# range_cape.net
KiCad netlist of a schematic drawn in EAGLE
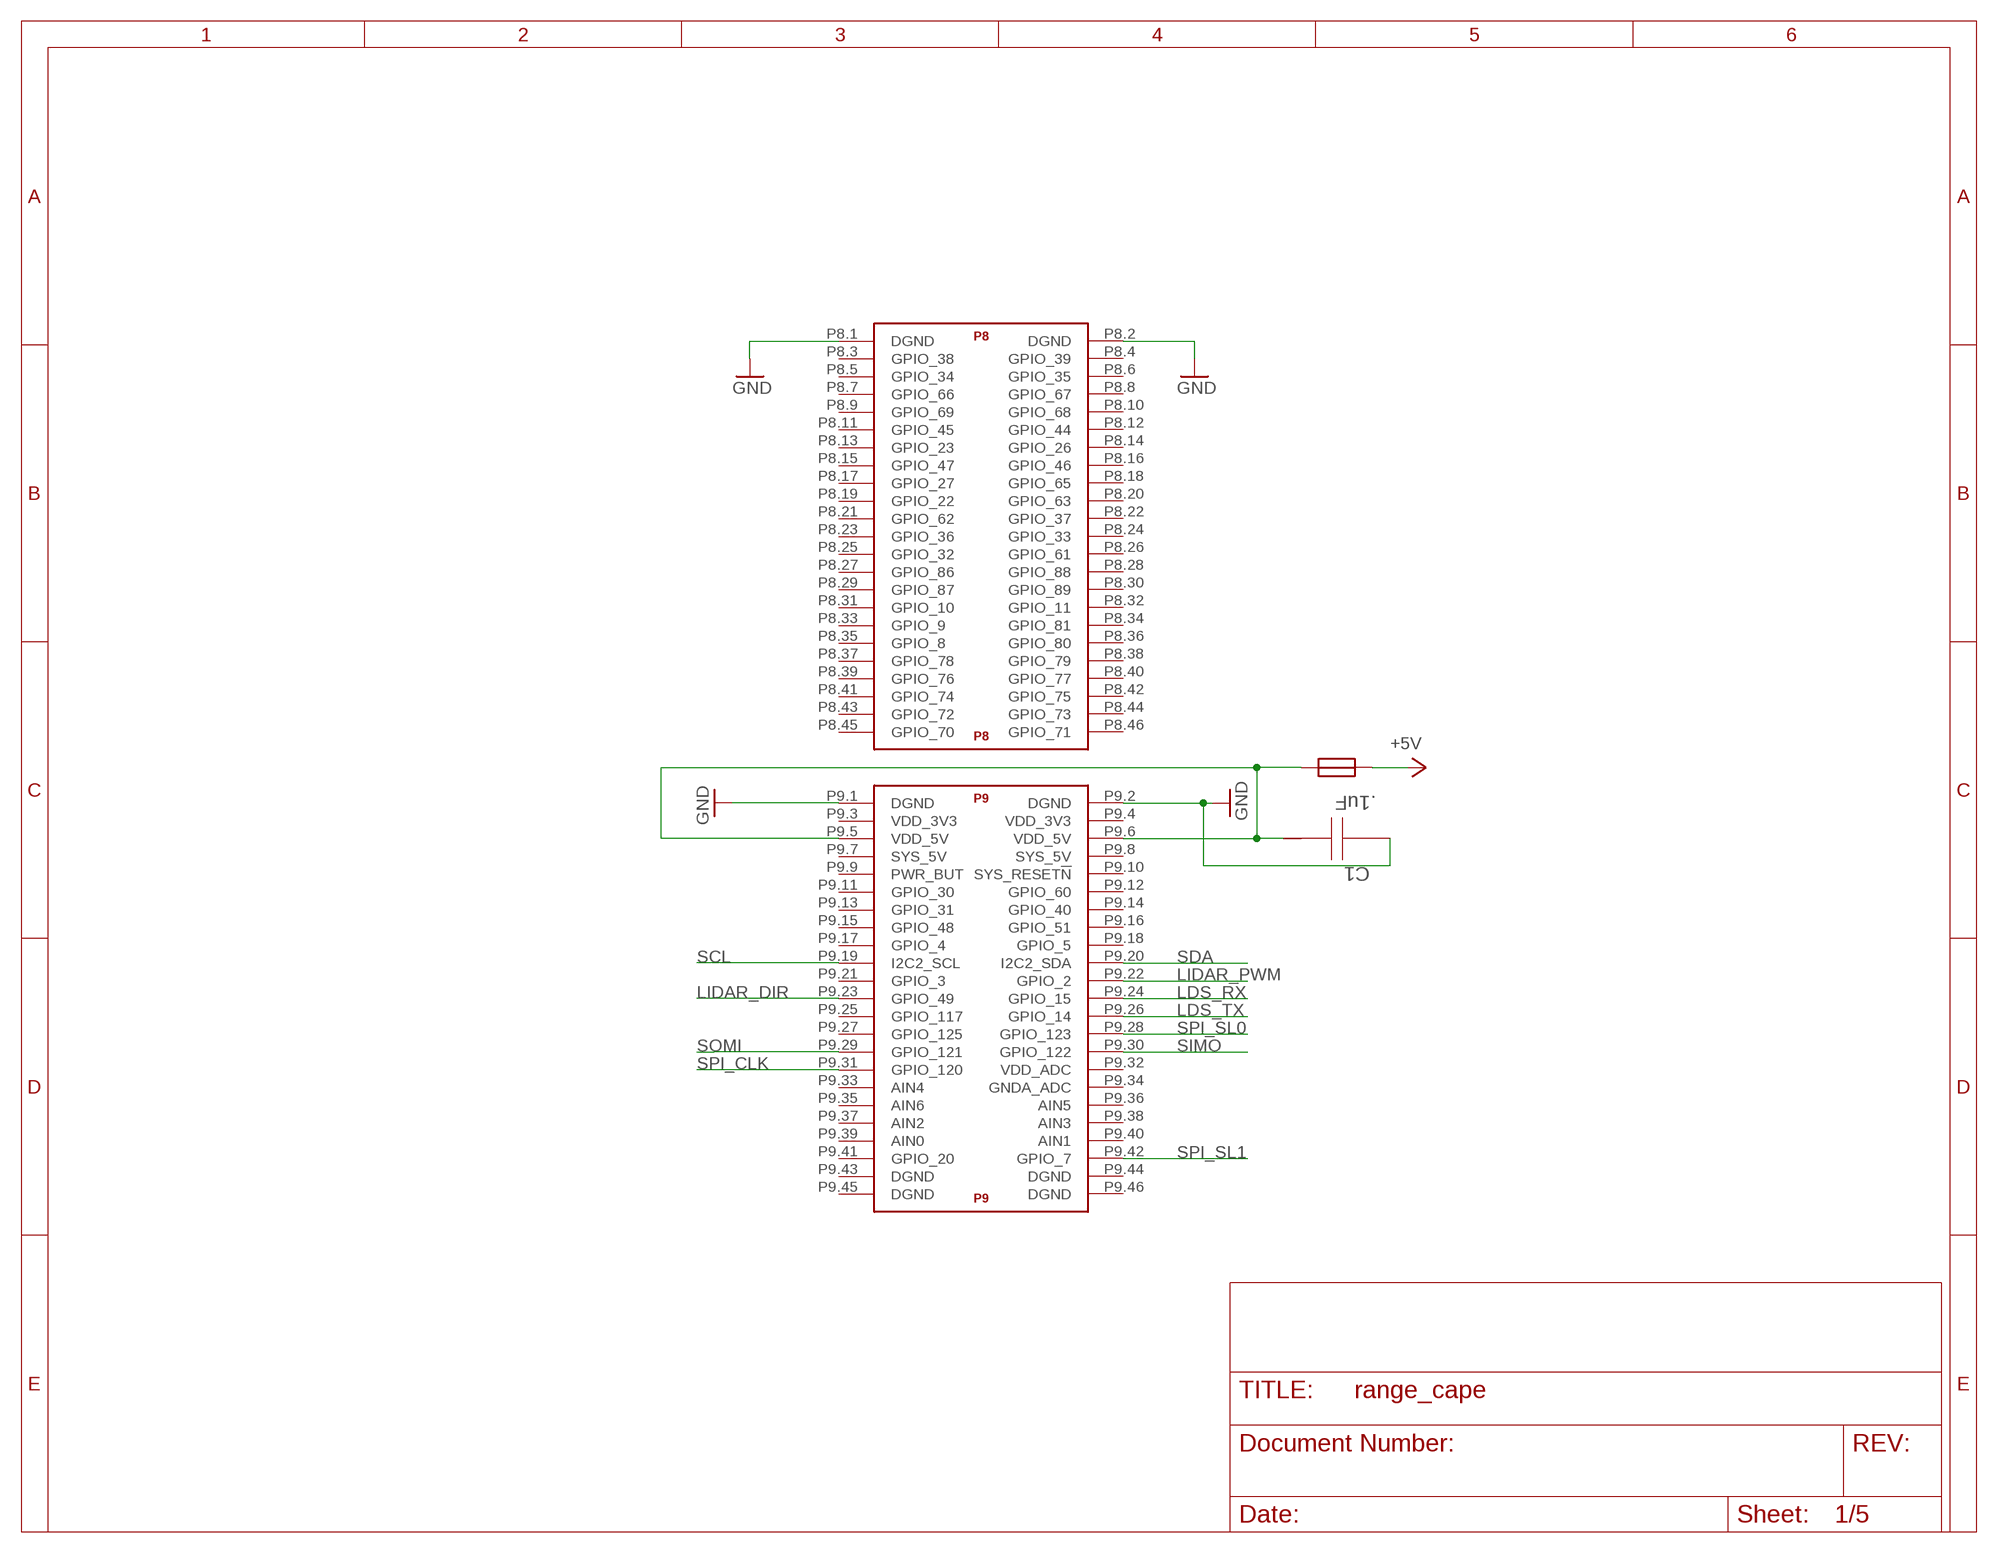
[diagram p0: schematic, sheet 1]
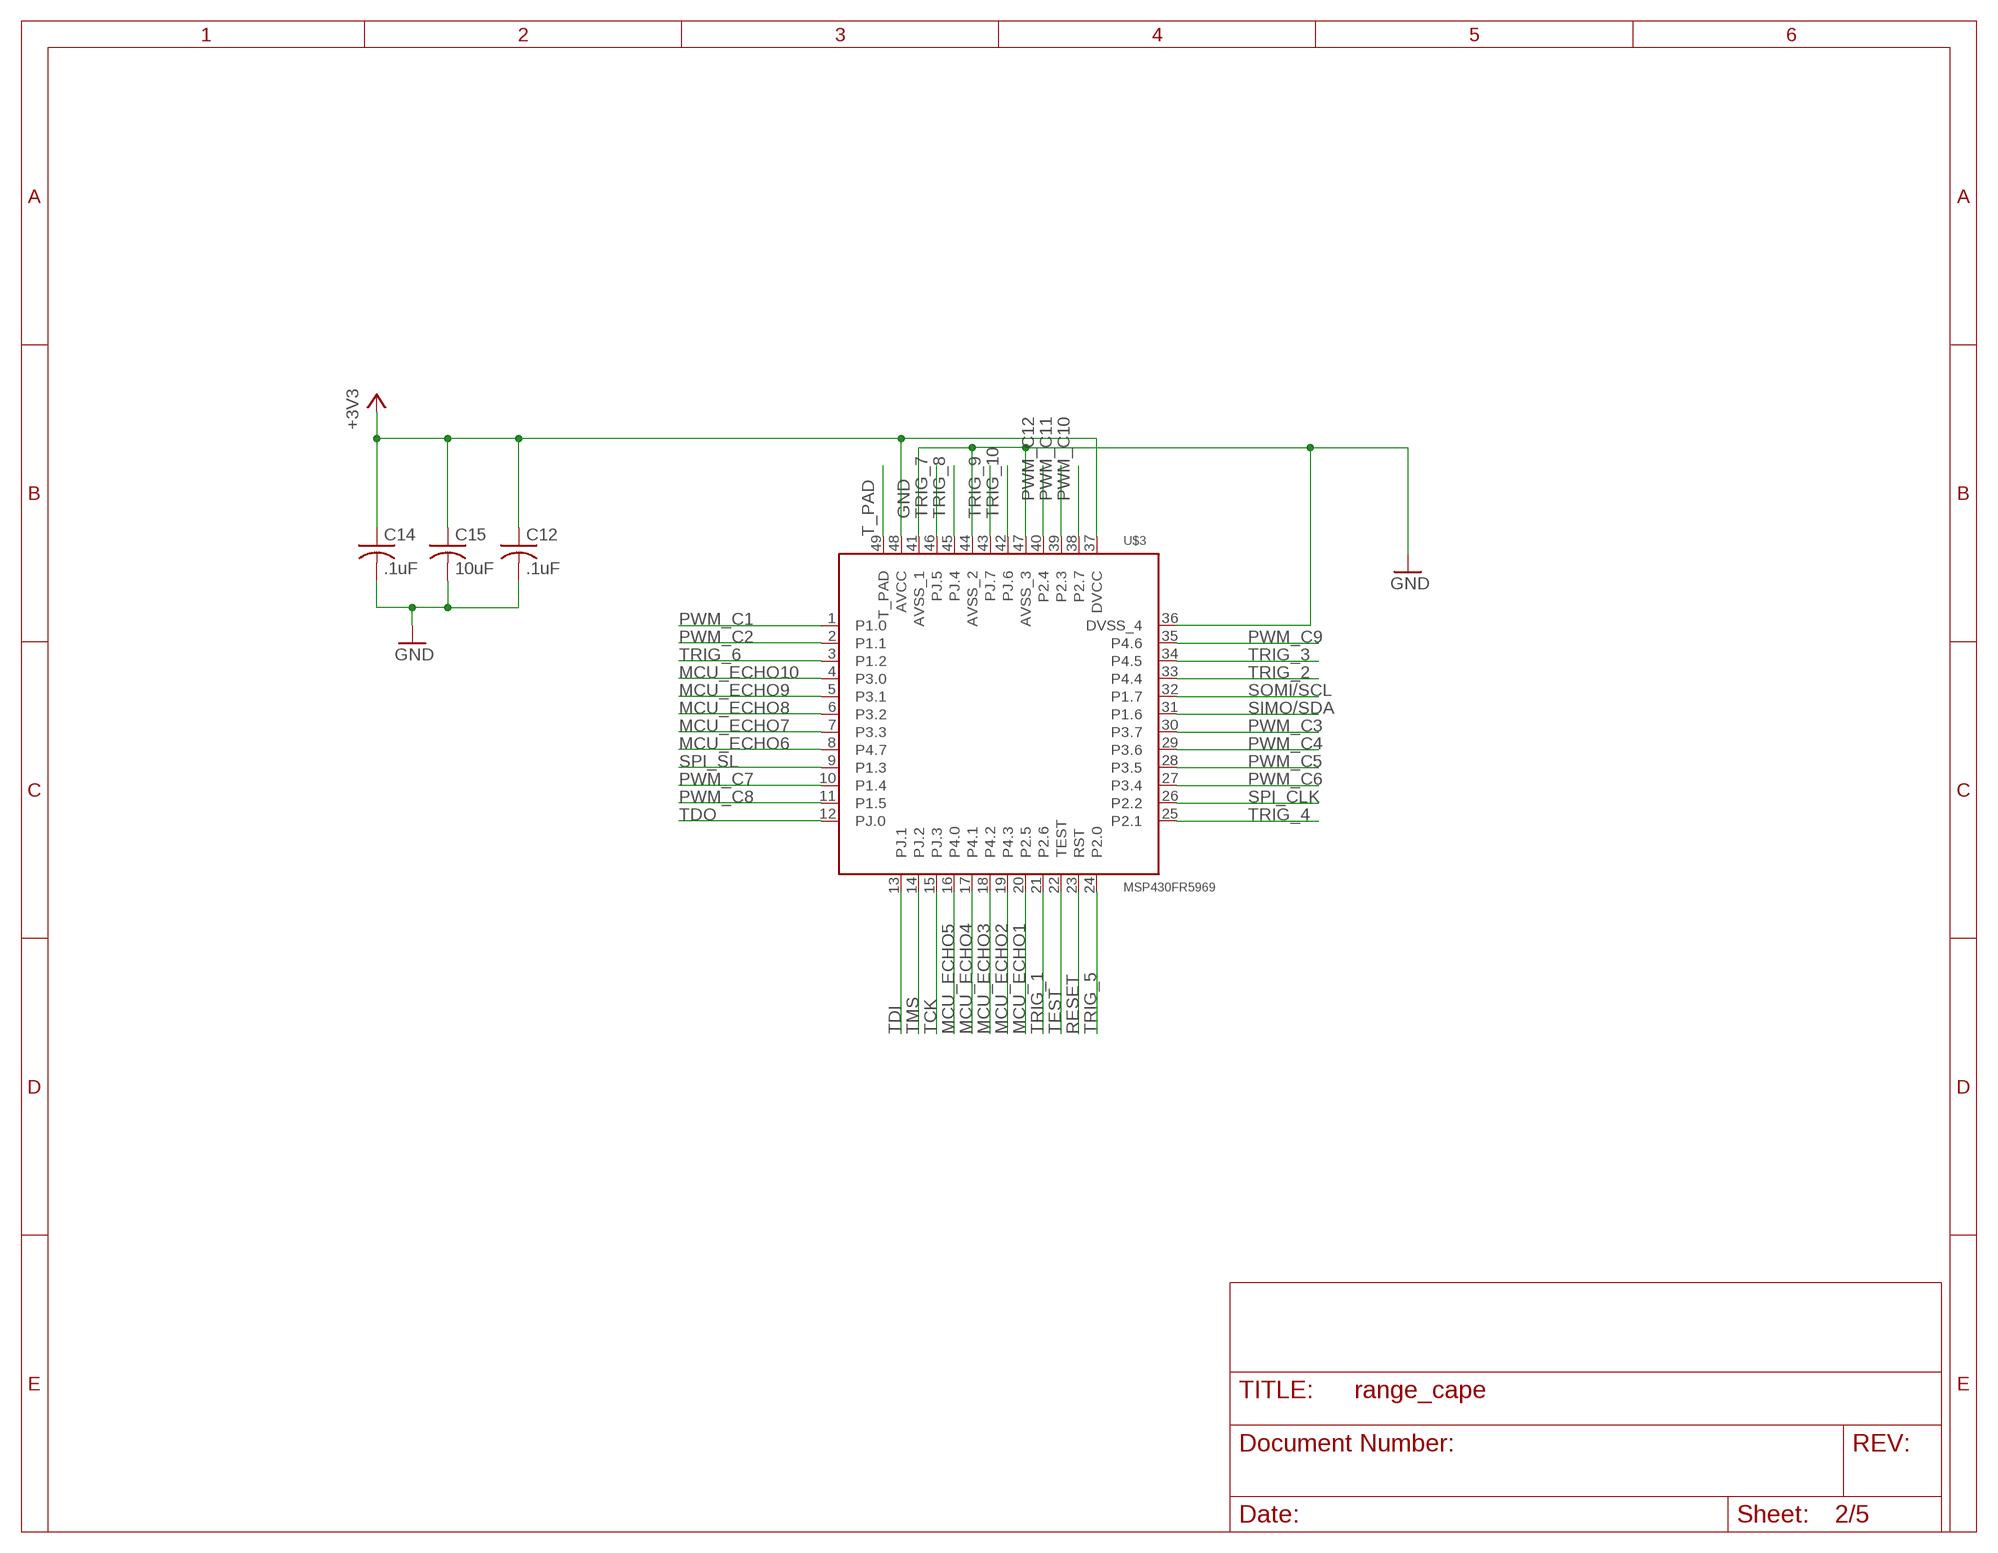
[diagram p1: schematic, sheet 2]
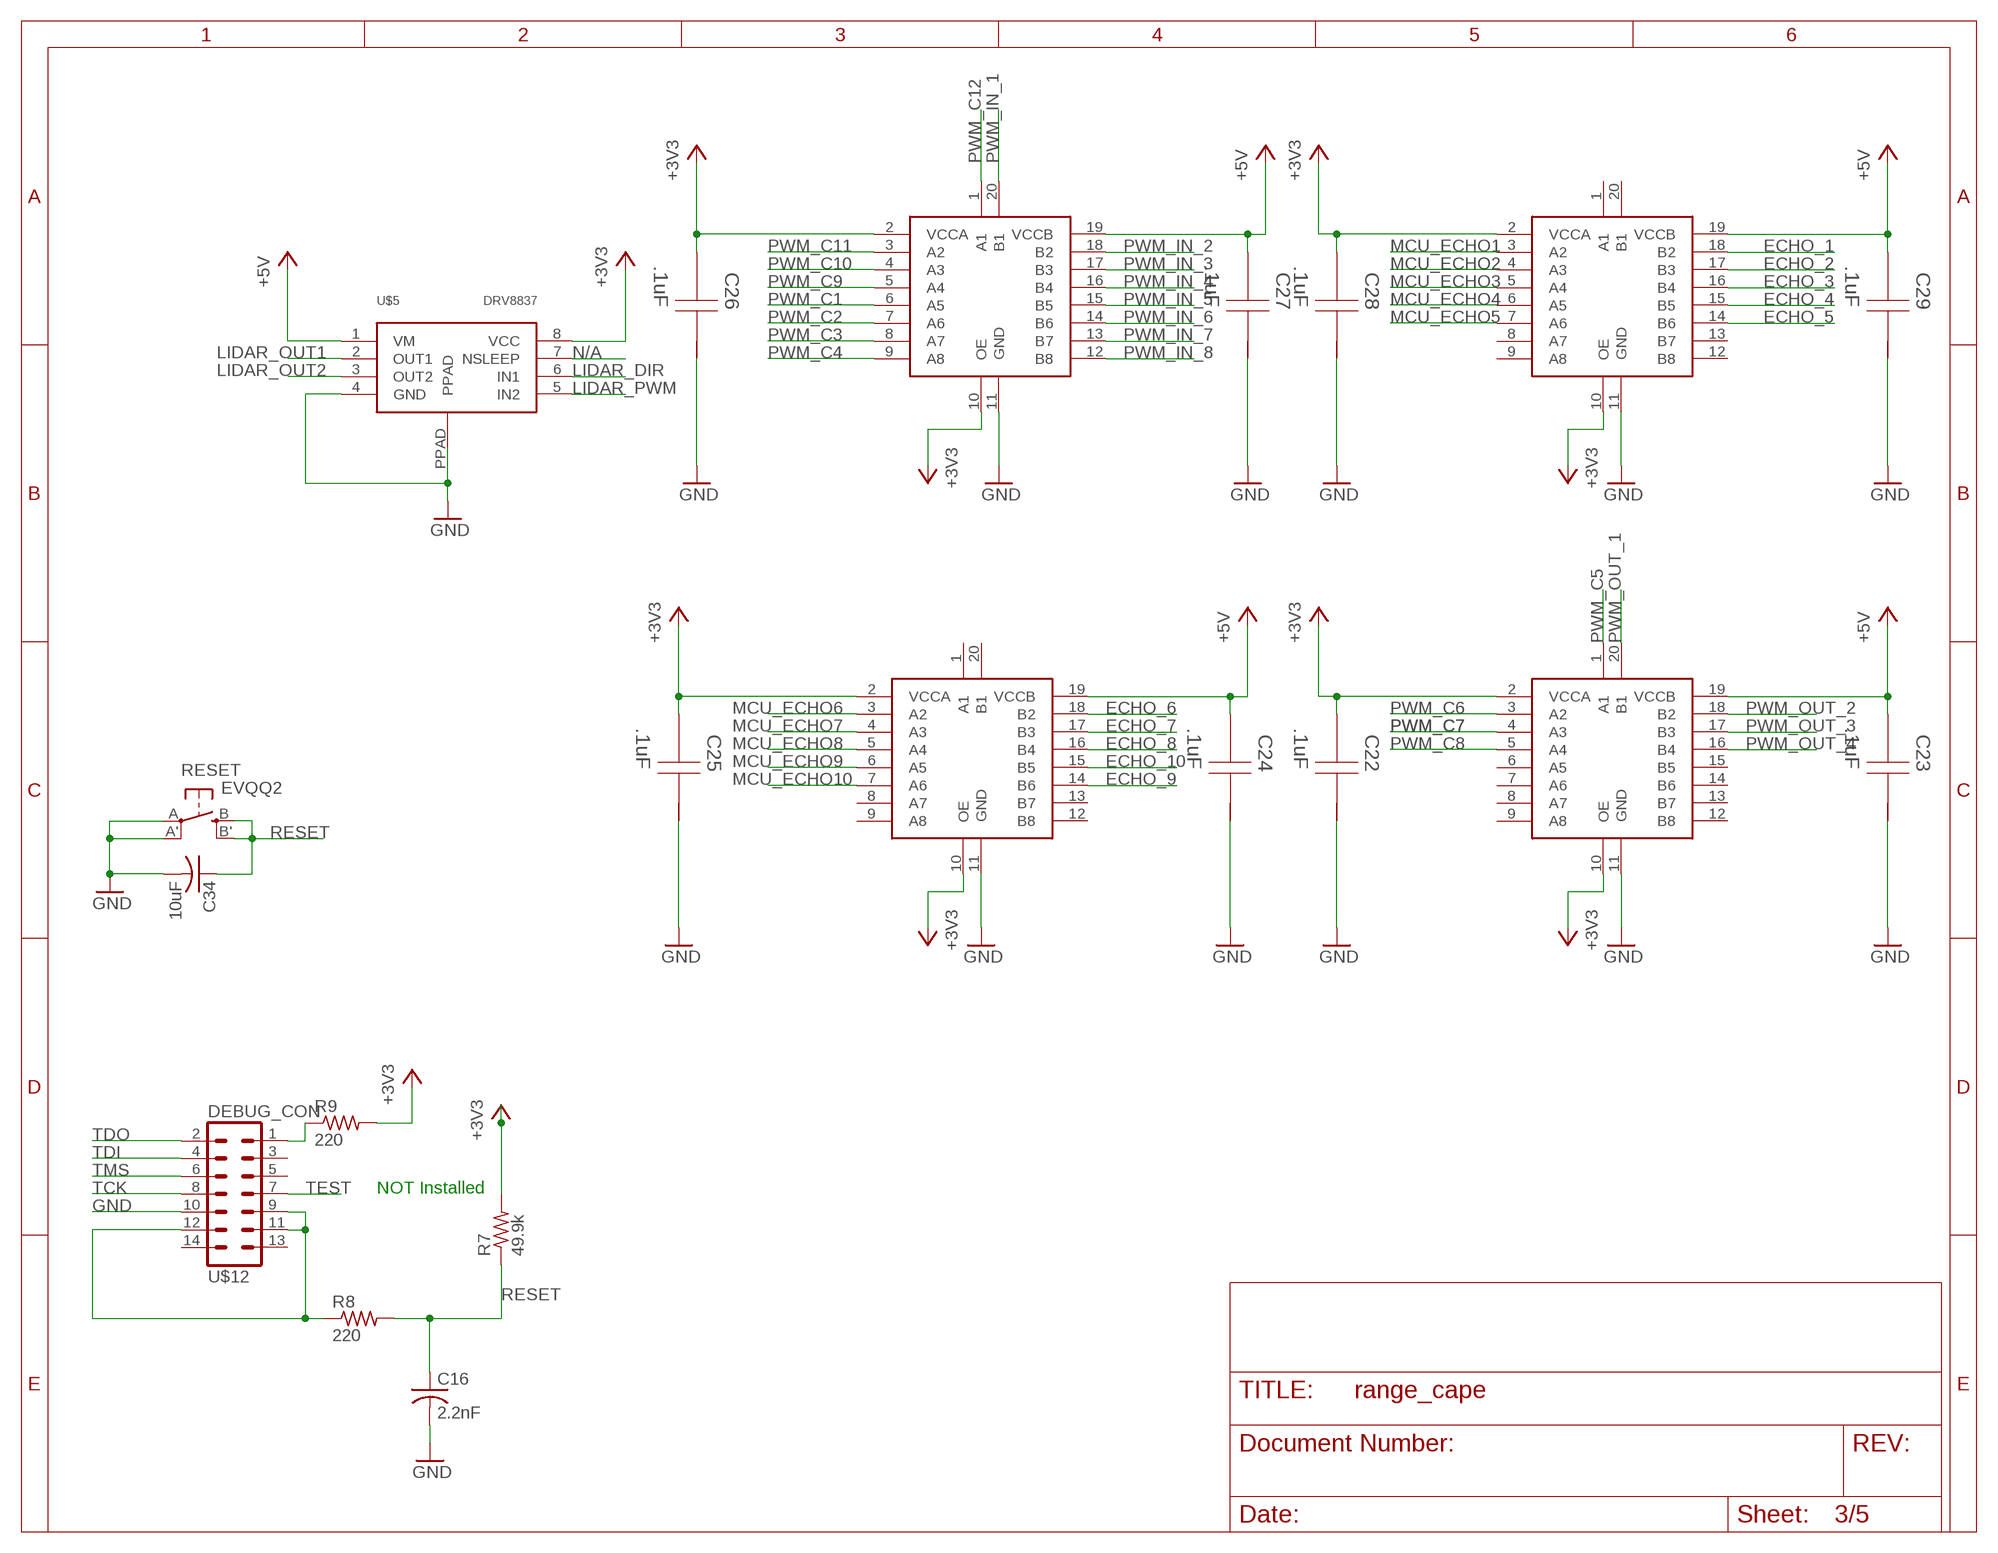
[diagram p2: schematic, sheet 3]
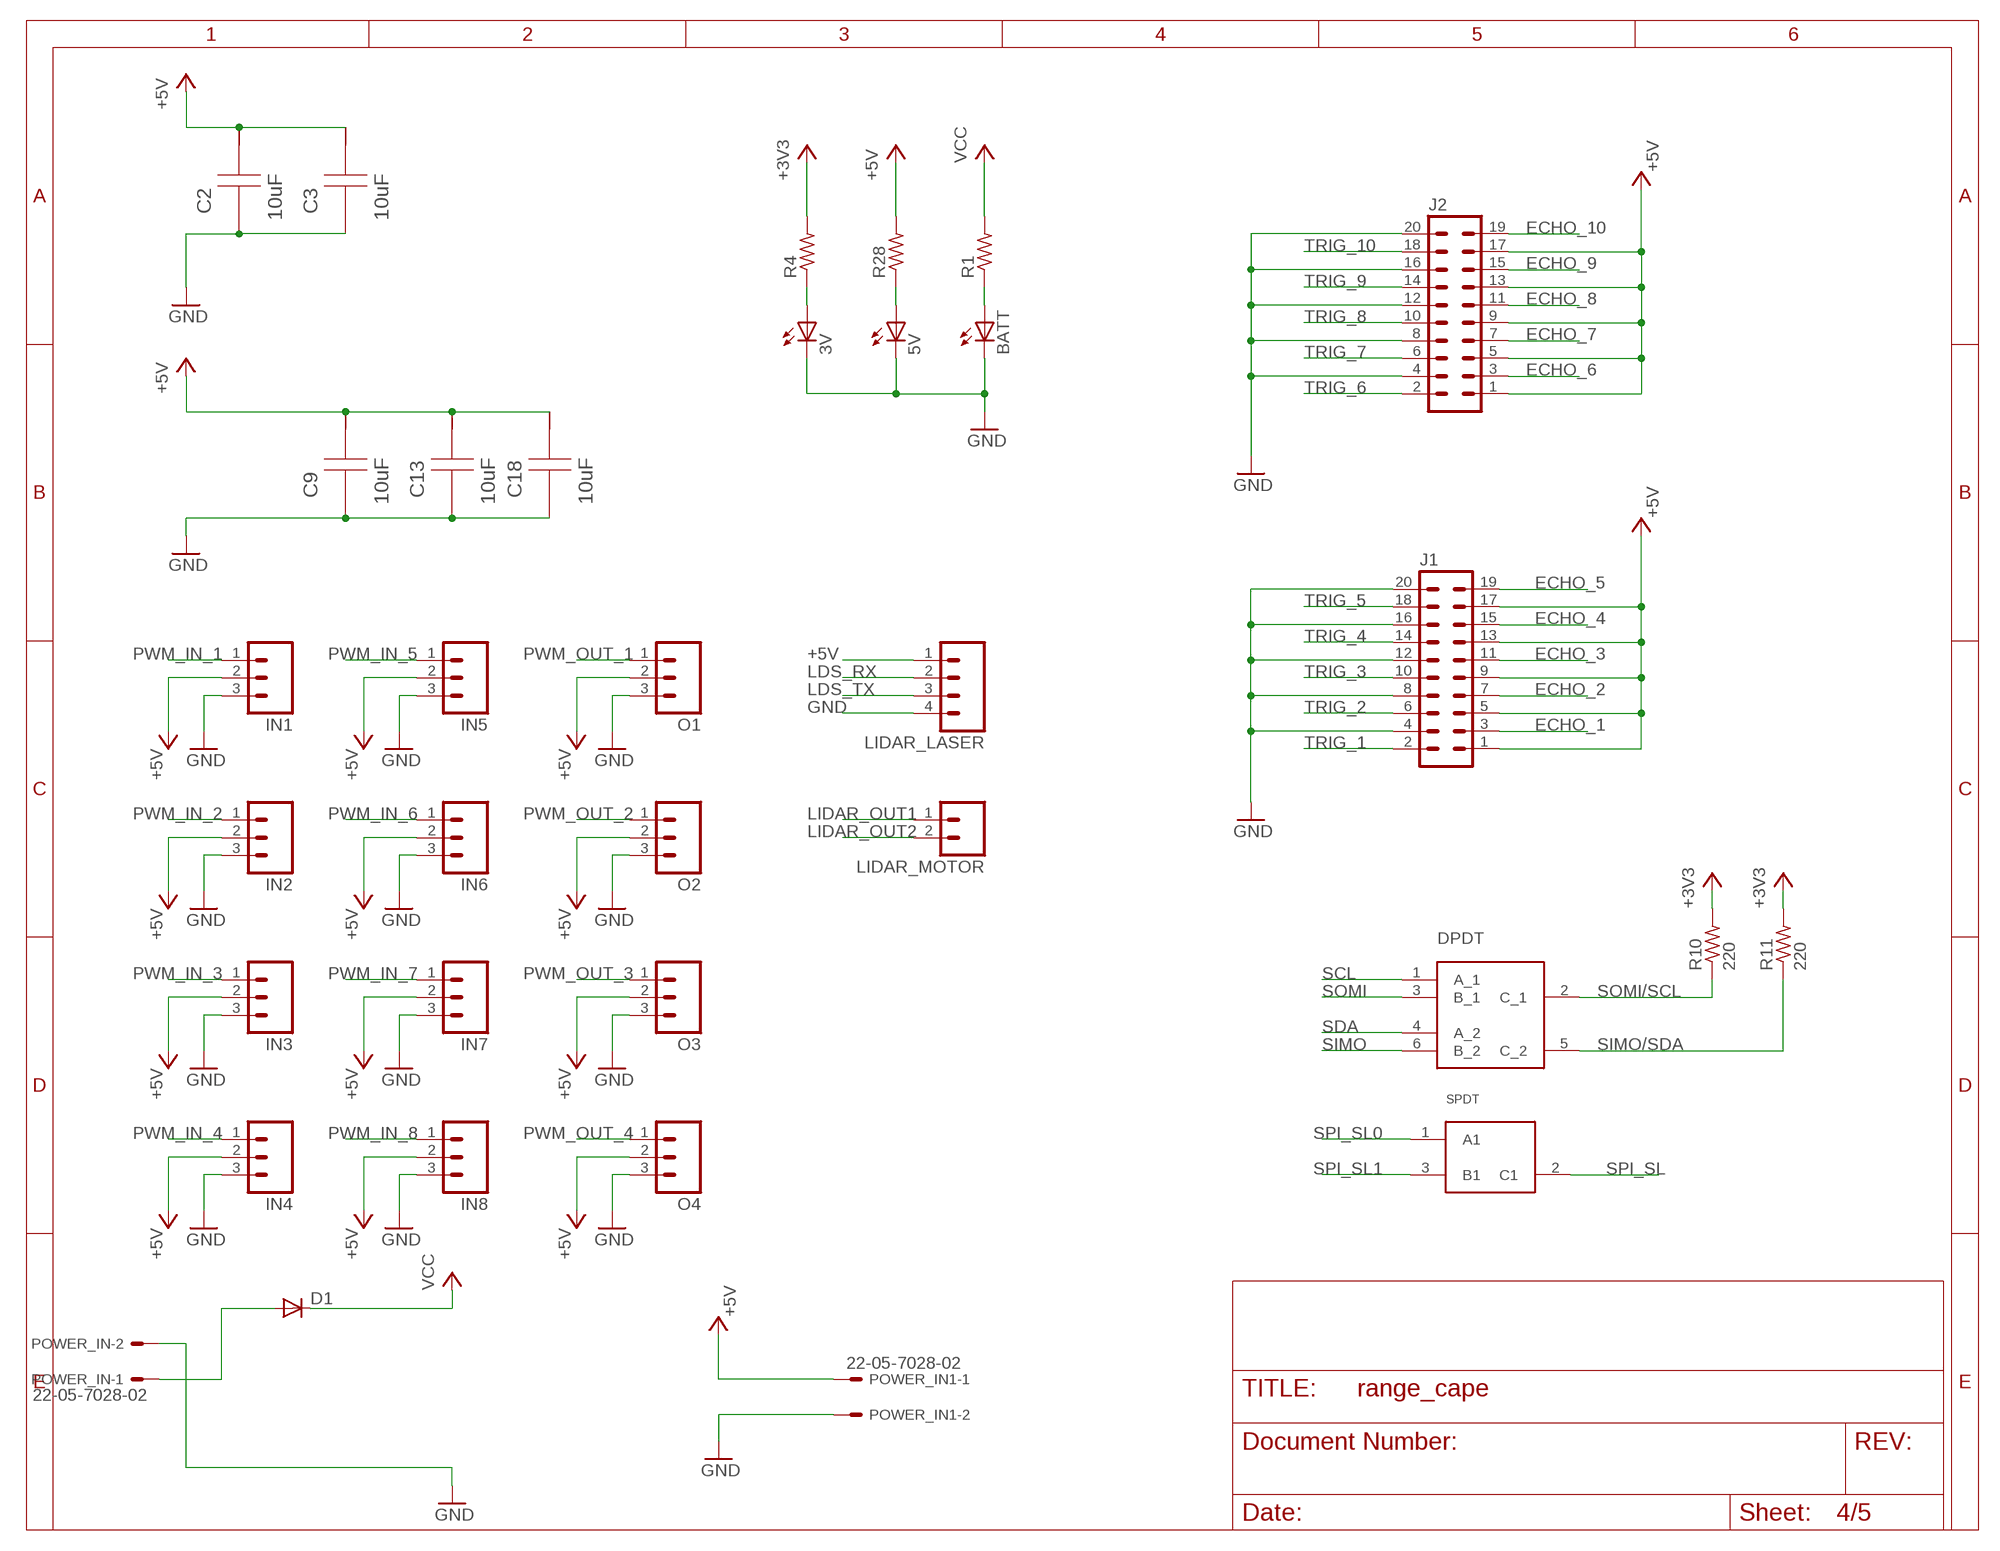
[diagram p3: schematic, sheet 4]
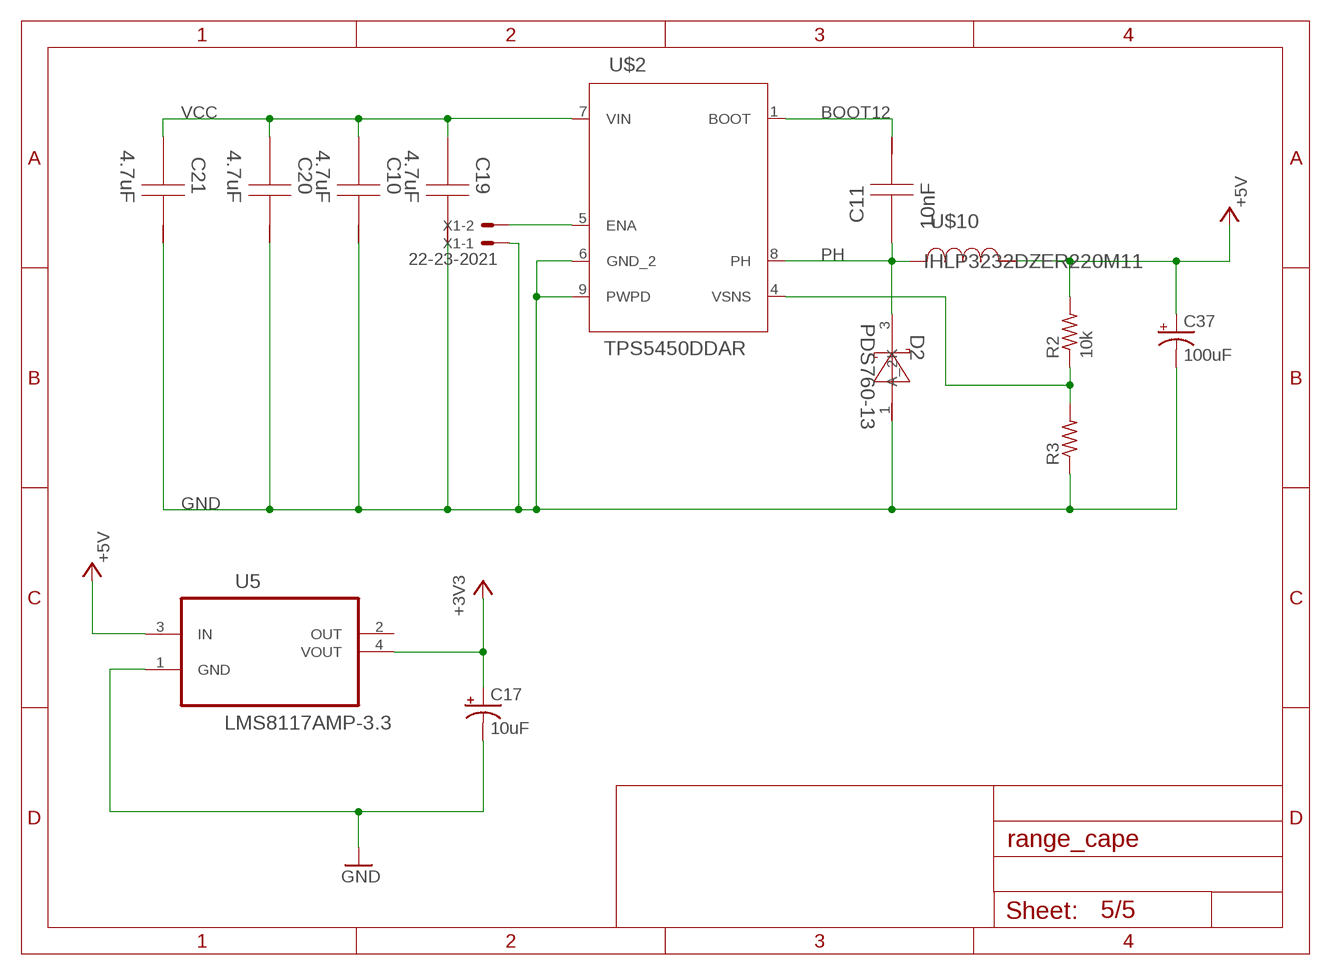
[diagram p4: schematic, sheet 5]

(export (version "E")
  (design (tool "Eeschema 10.0.6"))
  (components
    (comp (ref "C1")
      (value ".1uF")
      (footprint "eagle-import:1206")
      (fields (field (name "MANUFACTURER_PART_NUMBER") "C3216X5R1A106K"))
      (libsource (lib "eagle-import") (part "C3216X5R1A106K"))
    )
    (comp (ref "U$1")
      (value "BEAGLE_BONE_BLACK_CAPE")
      (footprint "eagle-import:BEAGLE_BONE_BLACK_CAPE")
      (libsource (lib "eagle-import") (part "BEAGLE_BONE_BLACK_CAPE"))
    )
    (comp (ref "U$11")
      (value "NANO_FUSE")
      (footprint "eagle-import:NANO_FUSE")
      (libsource (lib "eagle-import") (part "NANO_FUSE"))
    )
    (comp (ref "3V")
      (value "LED_ESML0603")
      (footprint "eagle-import:LED_SML0603")
      (libsource (lib "eagle-import") (part "LED_ESML0603"))
    )
    (comp (ref "5V")
      (value "LED_ESML0603")
      (footprint "eagle-import:LED_SML0603")
      (libsource (lib "eagle-import") (part "LED_ESML0603"))
    )
    (comp (ref "BATT")
      (value "LED_ESML0603")
      (footprint "eagle-import:LED_SML0603")
      (libsource (lib "eagle-import") (part "LED_ESML0603"))
    )
    (comp (ref "C2")
      (value "10uF")
      (footprint "eagle-import:1206")
      (fields (field (name "MANUFACTURER_PART_NUMBER") "C3216X5R1A106K"))
      (libsource (lib "eagle-import") (part "C3216X5R1A106K"))
    )
    (comp (ref "C3")
      (value "10uF")
      (footprint "eagle-import:1206")
      (fields (field (name "MANUFACTURER_PART_NUMBER") "C3216X5R1A106K"))
      (libsource (lib "eagle-import") (part "C3216X5R1A106K"))
    )
    (comp (ref "C9")
      (value "10uF")
      (footprint "eagle-import:1206")
      (fields (field (name "MANUFACTURER_PART_NUMBER") "C3216X5R1A106K"))
      (libsource (lib "eagle-import") (part "C3216X5R1A106K"))
    )
    (comp (ref "C13")
      (value "10uF")
      (footprint "eagle-import:1206")
      (fields (field (name "MANUFACTURER_PART_NUMBER") "C3216X5R1A106K"))
      (libsource (lib "eagle-import") (part "C3216X5R1A106K"))
    )
    (comp (ref "C18")
      (value "10uF")
      (footprint "eagle-import:1206")
      (fields (field (name "MANUFACTURER_PART_NUMBER") "C3216X5R1A106K"))
      (libsource (lib "eagle-import") (part "C3216X5R1A106K"))
    )
    (comp (ref "D1")
      (value "DIODE-DO-214AC")
      (footprint "eagle-import:DO-214AC")
      (libsource (lib "eagle-import") (part "DIODE-DO-214AC"))
    )
    (comp (ref "IN1")
      (value "M03LOCK")
      (footprint "eagle-import:1X03_LOCK")
      (libsource (lib "eagle-import") (part "M03LOCK"))
    )
    (comp (ref "IN2")
      (value "M03LOCK")
      (footprint "eagle-import:1X03_LOCK")
      (libsource (lib "eagle-import") (part "M03LOCK"))
    )
    (comp (ref "IN3")
      (value "M03LOCK")
      (footprint "eagle-import:1X03_LOCK")
      (libsource (lib "eagle-import") (part "M03LOCK"))
    )
    (comp (ref "IN4")
      (value "M03LOCK")
      (footprint "eagle-import:1X03_LOCK")
      (libsource (lib "eagle-import") (part "M03LOCK"))
    )
    (comp (ref "IN5")
      (value "M03LOCK")
      (footprint "eagle-import:1X03_LOCK")
      (libsource (lib "eagle-import") (part "M03LOCK"))
    )
    (comp (ref "IN6")
      (value "M03LOCK")
      (footprint "eagle-import:1X03_LOCK")
      (libsource (lib "eagle-import") (part "M03LOCK"))
    )
    (comp (ref "IN7")
      (value "M03LOCK")
      (footprint "eagle-import:1X03_LOCK")
      (libsource (lib "eagle-import") (part "M03LOCK"))
    )
    (comp (ref "IN8")
      (value "M03LOCK")
      (footprint "eagle-import:1X03_LOCK")
      (libsource (lib "eagle-import") (part "M03LOCK"))
    )
    (comp (ref "J1")
      (value "MA10-2")
      (footprint "eagle-import:MA10-2")
      (libsource (lib "eagle-import") (part "MA10-2"))
    )
    (comp (ref "J2")
      (value "MA10-2")
      (footprint "eagle-import:MA10-2")
      (libsource (lib "eagle-import") (part "MA10-2"))
    )
    (comp (ref "LIDAR_LASER")
      (value "M04JST-PTH-VERT")
      (footprint "eagle-import:JST-4-PTH-VERT")
      (libsource (lib "eagle-import") (part "M04JST-PTH-VERT"))
    )
    (comp (ref "LIDAR_MOTOR")
      (value "M02JST-PTH-VERT")
      (footprint "eagle-import:JST-2-PTH-VERT")
      (libsource (lib "eagle-import") (part "M02JST-PTH-VERT"))
    )
    (comp (ref "O1")
      (value "M03LOCK")
      (footprint "eagle-import:1X03_LOCK")
      (libsource (lib "eagle-import") (part "M03LOCK"))
    )
    (comp (ref "O2")
      (value "M03LOCK")
      (footprint "eagle-import:1X03_LOCK")
      (libsource (lib "eagle-import") (part "M03LOCK"))
    )
    (comp (ref "O3")
      (value "M03LOCK")
      (footprint "eagle-import:1X03_LOCK")
      (libsource (lib "eagle-import") (part "M03LOCK"))
    )
    (comp (ref "O4")
      (value "M03LOCK")
      (footprint "eagle-import:1X03_LOCK")
      (libsource (lib "eagle-import") (part "M03LOCK"))
    )
    (comp (ref "POWER_IN")
      (value "22-05-7028-02")
      (footprint "eagle-import:7395-02")
      (libsource (lib "eagle-import") (part "22-?-0205-7028"))
    )
    (comp (ref "POWER_IN1")
      (value "22-05-7028-02")
      (footprint "eagle-import:7395-02")
      (libsource (lib "eagle-import") (part "22-?-0205-7028"))
    )
    (comp (ref "R1")
      (value "R-US_R0603")
      (footprint "eagle-import:R0603")
      (libsource (lib "eagle-import") (part "rcl_R-US_R0603"))
    )
    (comp (ref "R4")
      (value "R-US_R0603")
      (footprint "eagle-import:R0603")
      (libsource (lib "eagle-import") (part "rcl_R-US_R0603"))
    )
    (comp (ref "R10")
      (value "220")
      (footprint "eagle-import:R0402")
      (libsource (lib "eagle-import") (part "rcl_R-US_R0402"))
    )
    (comp (ref "R11")
      (value "220")
      (footprint "eagle-import:R0402")
      (libsource (lib "eagle-import") (part "rcl_R-US_R0402"))
    )
    (comp (ref "R28")
      (value "R-US_R0603")
      (footprint "eagle-import:R0603")
      (libsource (lib "eagle-import") (part "rcl_R-US_R0603"))
    )
    (comp (ref "SPDT")
      (value "SPDT_SWITCH")
      (footprint "eagle-import:SPDT")
      (libsource (lib "eagle-import") (part "SPDT_SWITCH"))
    )
    (comp (ref "U$4")
      (value "DPDT_I2C_SPI")
      (footprint "eagle-import:DPDT")
      (libsource (lib "eagle-import") (part "DPDT_I2C_SPI"))
    )
    (comp (ref "C10")
      (value "4.7uF")
      (footprint "eagle-import:1206")
      (fields (field (name "MANUFACTURER_PART_NUMBER") "GRM31CR71H475KA12L"))
      (libsource (lib "eagle-import") (part "GRM31CR71H475KA12L"))
    )
    (comp (ref "C11")
      (value "10nF")
      (footprint "eagle-import:0805")
      (fields (field (name "MANUFACTURER_PART_NUMBER") "C0805C103K5RACTU"))
      (libsource (lib "eagle-import") (part "C0805C103K5RACTU"))
    )
    (comp (ref "C17")
      (value "10uF")
      (footprint "eagle-import:EIA3216")
      (libsource (lib "eagle-import") (part "10UF-16V-10%(TANT)"))
    )
    (comp (ref "C19")
      (value "4.7uF")
      (footprint "eagle-import:1206")
      (fields (field (name "MANUFACTURER_PART_NUMBER") "GRM31CR71H475KA12L"))
      (libsource (lib "eagle-import") (part "GRM31CR71H475KA12L"))
    )
    (comp (ref "C20")
      (value "4.7uF")
      (footprint "eagle-import:1206")
      (fields (field (name "MANUFACTURER_PART_NUMBER") "GRM31CR71H475KA12L"))
      (libsource (lib "eagle-import") (part "GRM31CR71H475KA12L"))
    )
    (comp (ref "C21")
      (value "4.7uF")
      (footprint "eagle-import:1206")
      (fields (field (name "MANUFACTURER_PART_NUMBER") "GRM31CR71H475KA12L"))
      (libsource (lib "eagle-import") (part "GRM31CR71H475KA12L"))
    )
    (comp (ref "C37")
      (value "100uF")
      (footprint "eagle-import:EIA7343")
      (libsource (lib "eagle-import") (part "100UF-10V-10%(TANT)"))
    )
    (comp (ref "D2")
      (value "PDS760-13")
      (footprint "eagle-import:POWERDI5")
      (libsource (lib "eagle-import") (part "PDS760-13"))
    )
    (comp (ref "R2")
      (value "10k")
      (footprint "eagle-import:M0805")
      (libsource (lib "eagle-import") (part "R-US_M0805"))
    )
    (comp (ref "R3")
      (value "R-US_M0805")
      (footprint "eagle-import:M0805")
      (libsource (lib "eagle-import") (part "R-US_M0805"))
    )
    (comp (ref "U$2")
      (value "TPS5450DDAR")
      (footprint "eagle-import:R-PDSO-G8")
      (fields (field (name "MANUFACTURER_PART_NUMBER") "TPS5450DDA"))
      (libsource (lib "eagle-import") (part "TPS5450DDAR"))
    )
    (comp (ref "U$10")
      (value "IHLP3232DZER220M11")
      (footprint "eagle-import:IHLP-3232DZ")
      (fields (field (name "MANUFACTURER") "Vishay"))
      (libsource (lib "eagle-import") (part "IHLP3232DZER220M11"))
    )
    (comp (ref "U5")
      (value "LMS8117AMP-3.3")
      (footprint "eagle-import:SOT230P696X180-4N")
      (libsource (lib "eagle-import") (part "LMS8117AMP-3.3"))
    )
    (comp (ref "X1")
      (value "22-23-2021")
      (footprint "eagle-import:22-23-2021")
      (fields (field (name "MF") "MOLEX"))
      (libsource (lib "eagle-import") (part "22-23-2021"))
    )
    (comp (ref "C12")
      (value ".1uF")
      (footprint "eagle-import:C0805")
      (libsource (lib "eagle-import") (part "C-USC0805"))
    )
    (comp (ref "C14")
      (value ".1uF")
      (footprint "eagle-import:C0805")
      (libsource (lib "eagle-import") (part "C-USC0805"))
    )
    (comp (ref "C15")
      (value "10uF")
      (footprint "eagle-import:C0805")
      (libsource (lib "eagle-import") (part "C-USC0805"))
    )
    (comp (ref "U$3")
      (value "MSP430FR5969")
      (footprint "eagle-import:QFN50P700X700X100-49N")
      (libsource (lib "eagle-import") (part "MSP430FR5969"))
    )
    (comp (ref "C16")
      (value "2.2nF")
      (footprint "eagle-import:C0603")
      (libsource (lib "eagle-import") (part "C-USC0603"))
    )
    (comp (ref "C22")
      (value ".1uF")
      (footprint "eagle-import:1206")
      (fields (field (name "MANUFACTURER_PART_NUMBER") "C3216X5R1A106K"))
      (libsource (lib "eagle-import") (part "C3216X5R1A106K"))
    )
    (comp (ref "C23")
      (value ".1uF")
      (footprint "eagle-import:1206")
      (fields (field (name "MANUFACTURER_PART_NUMBER") "C3216X5R1A106K"))
      (libsource (lib "eagle-import") (part "C3216X5R1A106K"))
    )
    (comp (ref "C24")
      (value ".1uF")
      (footprint "eagle-import:1206")
      (fields (field (name "MANUFACTURER_PART_NUMBER") "C3216X5R1A106K"))
      (libsource (lib "eagle-import") (part "C3216X5R1A106K"))
    )
    (comp (ref "C25")
      (value ".1uF")
      (footprint "eagle-import:1206")
      (fields (field (name "MANUFACTURER_PART_NUMBER") "C3216X5R1A106K"))
      (libsource (lib "eagle-import") (part "C3216X5R1A106K"))
    )
    (comp (ref "C26")
      (value ".1uF")
      (footprint "eagle-import:1206")
      (fields (field (name "MANUFACTURER_PART_NUMBER") "C3216X5R1A106K"))
      (libsource (lib "eagle-import") (part "C3216X5R1A106K"))
    )
    (comp (ref "C27")
      (value ".1uF")
      (footprint "eagle-import:1206")
      (fields (field (name "MANUFACTURER_PART_NUMBER") "C3216X5R1A106K"))
      (libsource (lib "eagle-import") (part "C3216X5R1A106K"))
    )
    (comp (ref "C28")
      (value ".1uF")
      (footprint "eagle-import:1206")
      (fields (field (name "MANUFACTURER_PART_NUMBER") "C3216X5R1A106K"))
      (libsource (lib "eagle-import") (part "C3216X5R1A106K"))
    )
    (comp (ref "C29")
      (value ".1uF")
      (footprint "eagle-import:1206")
      (fields (field (name "MANUFACTURER_PART_NUMBER") "C3216X5R1A106K"))
      (libsource (lib "eagle-import") (part "C3216X5R1A106K"))
    )
    (comp (ref "C34")
      (value "10uF")
      (footprint "eagle-import:C1206")
      (libsource (lib "eagle-import") (part "C-USC1206"))
    )
    (comp (ref "R7")
      (value "49.9k")
      (footprint "eagle-import:R0603")
      (libsource (lib "eagle-import") (part "rcl_R-US_R0603"))
    )
    (comp (ref "R8")
      (value "220")
      (footprint "eagle-import:R0603")
      (libsource (lib "eagle-import") (part "rcl_R-US_R0603"))
    )
    (comp (ref "R9")
      (value "220")
      (footprint "eagle-import:R0603")
      (libsource (lib "eagle-import") (part "rcl_R-US_R0603"))
    )
    (comp (ref "RESET")
      (value "EVQQ2")
      (footprint "eagle-import:EVQ-Q2")
      (libsource (lib "eagle-import") (part "EVQQ2"))
    )
    (comp (ref "U$5")
      (value "DRV8837")
      (footprint "eagle-import:WSON-8")
      (libsource (lib "eagle-import") (part "DRV8837"))
    )
    (comp (ref "U$6")
      (value "TXB0108")
      (footprint "eagle-import:TSSOP-20")
      (libsource (lib "eagle-import") (part "TXB0108"))
    )
    (comp (ref "U$7")
      (value "TXB0108")
      (footprint "eagle-import:TSSOP-20")
      (libsource (lib "eagle-import") (part "TXB0108"))
    )
    (comp (ref "U$8")
      (value "TXB0108")
      (footprint "eagle-import:TSSOP-20")
      (libsource (lib "eagle-import") (part "TXB0108"))
    )
    (comp (ref "U$9")
      (value "TXB0108")
      (footprint "eagle-import:TSSOP-20")
      (libsource (lib "eagle-import") (part "TXB0108"))
    )
    (comp (ref "U$12")
      (value "DEBUG_CON")
      (footprint "eagle-import:DEBUG_SM")
      (libsource (lib "eagle-import") (part "DEBUG_CON"))
    )
  )
  (nets
    (net (code "1") (name "+3V3") (class "Default")
      (node (ref "C12") (pin "1") (pinfunction "1_1") (pintype "passive"))
      (node (ref "C14") (pin "1") (pinfunction "1_1") (pintype "passive"))
      (node (ref "C15") (pin "1") (pinfunction "1_1") (pintype "passive"))
      (node (ref "C17") (pin "A") (pinfunction "+_A") (pintype "passive"))
      (node (ref "C22") (pin "2") (pinfunction "2_2") (pintype "passive"))
      (node (ref "C25") (pin "2") (pinfunction "2_2") (pintype "passive"))
      (node (ref "C26") (pin "2") (pinfunction "2_2") (pintype "passive"))
      (node (ref "C28") (pin "2") (pinfunction "2_2") (pintype "passive"))
      (node (ref "R10") (pin "2") (pinfunction "2_2") (pintype "passive"))
      (node (ref "R11") (pin "2") (pinfunction "2_2") (pintype "passive"))
      (node (ref "R4") (pin "2") (pinfunction "2_2") (pintype "passive"))
      (node (ref "R7") (pin "2") (pinfunction "2_2") (pintype "passive"))
      (node (ref "R9") (pin "2") (pinfunction "2_2") (pintype "passive"))
      (node (ref "U$3") (pin "37") (pinfunction "DVCC_37") (pintype "power_in"))
      (node (ref "U$3") (pin "48") (pinfunction "AVCC_48") (pintype "power_in"))
      (node (ref "U$5") (pin "8") (pinfunction "VCC_8") (pintype "bidirectional"))
      (node (ref "U$6") (pin "10") (pinfunction "OE_10") (pintype "bidirectional"))
      (node (ref "U$6") (pin "2") (pinfunction "VCCA_2") (pintype "bidirectional"))
      (node (ref "U$7") (pin "10") (pinfunction "OE_10") (pintype "bidirectional"))
      (node (ref "U$7") (pin "2") (pinfunction "VCCA_2") (pintype "bidirectional"))
      (node (ref "U$8") (pin "10") (pinfunction "OE_10") (pintype "bidirectional"))
      (node (ref "U$8") (pin "2") (pinfunction "VCCA_2") (pintype "bidirectional"))
      (node (ref "U$9") (pin "10") (pinfunction "OE_10") (pintype "bidirectional"))
      (node (ref "U$9") (pin "2") (pinfunction "VCCA_2") (pintype "bidirectional"))
      (node (ref "U5") (pin "4") (pinfunction "VOUT_4") (pintype "power_in"))
    )
    (net (code "2") (name "+5V") (class "Default")
      (node (ref "C13") (pin "1") (pinfunction "1_1") (pintype "passive"))
      (node (ref "C18") (pin "1") (pinfunction "1_1") (pintype "passive"))
      (node (ref "C2") (pin "1") (pinfunction "1_1") (pintype "passive"))
      (node (ref "C23") (pin "2") (pinfunction "2_2") (pintype "passive"))
      (node (ref "C24") (pin "2") (pinfunction "2_2") (pintype "passive"))
      (node (ref "C27") (pin "2") (pinfunction "2_2") (pintype "passive"))
      (node (ref "C29") (pin "2") (pinfunction "2_2") (pintype "passive"))
      (node (ref "C3") (pin "1") (pinfunction "1_1") (pintype "passive"))
      (node (ref "C37") (pin "A") (pinfunction "+_A") (pintype "passive"))
      (node (ref "C9") (pin "1") (pinfunction "1_1") (pintype "passive"))
      (node (ref "IN1") (pin "2") (pinfunction "2_2") (pintype "passive"))
      (node (ref "IN2") (pin "2") (pinfunction "2_2") (pintype "passive"))
      (node (ref "IN3") (pin "2") (pinfunction "2_2") (pintype "passive"))
      (node (ref "IN4") (pin "2") (pinfunction "2_2") (pintype "passive"))
      (node (ref "IN5") (pin "2") (pinfunction "2_2") (pintype "passive"))
      (node (ref "IN6") (pin "2") (pinfunction "2_2") (pintype "passive"))
      (node (ref "IN7") (pin "2") (pinfunction "2_2") (pintype "passive"))
      (node (ref "IN8") (pin "2") (pinfunction "2_2") (pintype "passive"))
      (node (ref "J1") (pin "1") (pinfunction "1_1") (pintype "passive"))
      (node (ref "J1") (pin "13") (pinfunction "13_13") (pintype "passive"))
      (node (ref "J1") (pin "17") (pinfunction "17_17") (pintype "passive"))
      (node (ref "J1") (pin "5") (pinfunction "5_5") (pintype "passive"))
      (node (ref "J1") (pin "9") (pinfunction "9_9") (pintype "passive"))
      (node (ref "J2") (pin "1") (pinfunction "1_1") (pintype "passive"))
      (node (ref "J2") (pin "13") (pinfunction "13_13") (pintype "passive"))
      (node (ref "J2") (pin "17") (pinfunction "17_17") (pintype "passive"))
      (node (ref "J2") (pin "5") (pinfunction "5_5") (pintype "passive"))
      (node (ref "J2") (pin "9") (pinfunction "9_9") (pintype "passive"))
      (node (ref "LIDAR_LASER") (pin "1") (pinfunction "1_1") (pintype "passive"))
      (node (ref "O1") (pin "2") (pinfunction "2_2") (pintype "passive"))
      (node (ref "O2") (pin "2") (pinfunction "2_2") (pintype "passive"))
      (node (ref "O3") (pin "2") (pinfunction "2_2") (pintype "passive"))
      (node (ref "O4") (pin "2") (pinfunction "2_2") (pintype "passive"))
      (node (ref "POWER_IN1") (pin "1") (pinfunction "S_1") (pintype "passive"))
      (node (ref "R2") (pin "2") (pinfunction "2_2") (pintype "passive"))
      (node (ref "R28") (pin "2") (pinfunction "2_2") (pintype "passive"))
      (node (ref "U$10") (pin "2") (pinfunction "2_2") (pintype "passive"))
      (node (ref "U$11") (pin "2") (pinfunction "2_2") (pintype "bidirectional"))
      (node (ref "U$5") (pin "1") (pinfunction "VM_1") (pintype "bidirectional"))
      (node (ref "U$6") (pin "19") (pinfunction "VCCB_19") (pintype "bidirectional"))
      (node (ref "U$7") (pin "19") (pinfunction "VCCB_19") (pintype "bidirectional"))
      (node (ref "U$8") (pin "19") (pinfunction "VCCB_19") (pintype "bidirectional"))
      (node (ref "U$9") (pin "19") (pinfunction "VCCB_19") (pintype "bidirectional"))
      (node (ref "U5") (pin "3") (pinfunction "IN_3") (pintype "power_in"))
    )
    (net (code "3") (name "BOOT12") (class "Default")
      (node (ref "C11") (pin "1") (pinfunction "1_1") (pintype "passive"))
      (node (ref "U$2") (pin "1") (pinfunction "BOOT_1") (pintype "passive"))
    )
    (net (code "4") (name "ECHO_1") (class "Default")
      (node (ref "J1") (pin "3") (pinfunction "3_3") (pintype "passive"))
      (node (ref "U$6") (pin "18") (pinfunction "B2_18") (pintype "bidirectional"))
    )
    (net (code "5") (name "ECHO_2") (class "Default")
      (node (ref "J1") (pin "7") (pinfunction "7_7") (pintype "passive"))
      (node (ref "U$6") (pin "17") (pinfunction "B3_17") (pintype "bidirectional"))
    )
    (net (code "6") (name "ECHO_3") (class "Default")
      (node (ref "J1") (pin "11") (pinfunction "11_11") (pintype "passive"))
      (node (ref "U$6") (pin "16") (pinfunction "B4_16") (pintype "bidirectional"))
    )
    (net (code "7") (name "ECHO_4") (class "Default")
      (node (ref "J1") (pin "15") (pinfunction "15_15") (pintype "passive"))
      (node (ref "U$6") (pin "15") (pinfunction "B5_15") (pintype "bidirectional"))
    )
    (net (code "8") (name "ECHO_5") (class "Default")
      (node (ref "J1") (pin "19") (pinfunction "19_19") (pintype "passive"))
      (node (ref "U$6") (pin "14") (pinfunction "B6_14") (pintype "bidirectional"))
    )
    (net (code "9") (name "ECHO_6") (class "Default")
      (node (ref "J2") (pin "3") (pinfunction "3_3") (pintype "passive"))
      (node (ref "U$8") (pin "18") (pinfunction "B2_18") (pintype "bidirectional"))
    )
    (net (code "10") (name "ECHO_7") (class "Default")
      (node (ref "J2") (pin "7") (pinfunction "7_7") (pintype "passive"))
      (node (ref "U$8") (pin "17") (pinfunction "B3_17") (pintype "bidirectional"))
    )
    (net (code "11") (name "ECHO_8") (class "Default")
      (node (ref "J2") (pin "11") (pinfunction "11_11") (pintype "passive"))
      (node (ref "U$8") (pin "16") (pinfunction "B4_16") (pintype "bidirectional"))
    )
    (net (code "12") (name "ECHO_9") (class "Default")
      (node (ref "J2") (pin "15") (pinfunction "15_15") (pintype "passive"))
      (node (ref "U$8") (pin "14") (pinfunction "B6_14") (pintype "bidirectional"))
    )
    (net (code "13") (name "ECHO_10") (class "Default")
      (node (ref "J2") (pin "19") (pinfunction "19_19") (pintype "passive"))
      (node (ref "U$8") (pin "15") (pinfunction "B5_15") (pintype "bidirectional"))
    )
    (net (code "14") (name "GND") (class "Default")
      (node (ref "3V") (pin "C") (pinfunction "C_C") (pintype "passive"))
      (node (ref "5V") (pin "C") (pinfunction "C_C") (pintype "passive"))
      (node (ref "BATT") (pin "C") (pinfunction "C_C") (pintype "passive"))
      (node (ref "C1") (pin "2") (pinfunction "2_2") (pintype "passive"))
      (node (ref "C10") (pin "1") (pinfunction "1_1") (pintype "passive"))
      (node (ref "C12") (pin "2") (pinfunction "2_2") (pintype "passive"))
      (node (ref "C13") (pin "2") (pinfunction "2_2") (pintype "passive"))
      (node (ref "C14") (pin "2") (pinfunction "2_2") (pintype "passive"))
      (node (ref "C15") (pin "2") (pinfunction "2_2") (pintype "passive"))
      (node (ref "C16") (pin "2") (pinfunction "2_2") (pintype "passive"))
      (node (ref "C17") (pin "C") (pinfunction "-_C") (pintype "passive"))
      (node (ref "C18") (pin "2") (pinfunction "2_2") (pintype "passive"))
      (node (ref "C19") (pin "1") (pinfunction "1_1") (pintype "passive"))
      (node (ref "C2") (pin "2") (pinfunction "2_2") (pintype "passive"))
      (node (ref "C20") (pin "1") (pinfunction "1_1") (pintype "passive"))
      (node (ref "C21") (pin "1") (pinfunction "1_1") (pintype "passive"))
      (node (ref "C22") (pin "1") (pinfunction "1_1") (pintype "passive"))
      (node (ref "C23") (pin "1") (pinfunction "1_1") (pintype "passive"))
      (node (ref "C24") (pin "1") (pinfunction "1_1") (pintype "passive"))
      (node (ref "C25") (pin "1") (pinfunction "1_1") (pintype "passive"))
      (node (ref "C26") (pin "1") (pinfunction "1_1") (pintype "passive"))
      (node (ref "C27") (pin "1") (pinfunction "1_1") (pintype "passive"))
      (node (ref "C28") (pin "1") (pinfunction "1_1") (pintype "passive"))
      (node (ref "C29") (pin "1") (pinfunction "1_1") (pintype "passive"))
      (node (ref "C3") (pin "2") (pinfunction "2_2") (pintype "passive"))
      (node (ref "C34") (pin "2") (pinfunction "2_2") (pintype "passive"))
      (node (ref "C37") (pin "C") (pinfunction "-_C") (pintype "passive"))
      (node (ref "C9") (pin "2") (pinfunction "2_2") (pintype "passive"))
      (node (ref "D2") (pin "1") (pinfunction "A_2_1") (pintype "passive"))
      (node (ref "IN1") (pin "3") (pinfunction "3_3") (pintype "passive"))
      (node (ref "IN2") (pin "3") (pinfunction "3_3") (pintype "passive"))
      (node (ref "IN3") (pin "3") (pinfunction "3_3") (pintype "passive"))
      (node (ref "IN4") (pin "3") (pinfunction "3_3") (pintype "passive"))
      (node (ref "IN5") (pin "3") (pinfunction "3_3") (pintype "passive"))
      (node (ref "IN6") (pin "3") (pinfunction "3_3") (pintype "passive"))
      (node (ref "IN7") (pin "3") (pinfunction "3_3") (pintype "passive"))
      (node (ref "IN8") (pin "3") (pinfunction "3_3") (pintype "passive"))
      (node (ref "J1") (pin "12") (pinfunction "12_12") (pintype "passive"))
      (node (ref "J1") (pin "16") (pinfunction "16_16") (pintype "passive"))
      (node (ref "J1") (pin "20") (pinfunction "20_20") (pintype "passive"))
      (node (ref "J1") (pin "4") (pinfunction "4_4") (pintype "passive"))
      (node (ref "J1") (pin "8") (pinfunction "8_8") (pintype "passive"))
      (node (ref "J2") (pin "12") (pinfunction "12_12") (pintype "passive"))
      (node (ref "J2") (pin "16") (pinfunction "16_16") (pintype "passive"))
      (node (ref "J2") (pin "20") (pinfunction "20_20") (pintype "passive"))
      (node (ref "J2") (pin "4") (pinfunction "4_4") (pintype "passive"))
      (node (ref "J2") (pin "8") (pinfunction "8_8") (pintype "passive"))
      (node (ref "LIDAR_LASER") (pin "4") (pinfunction "4_4") (pintype "passive"))
      (node (ref "O1") (pin "3") (pinfunction "3_3") (pintype "passive"))
      (node (ref "O2") (pin "3") (pinfunction "3_3") (pintype "passive"))
      (node (ref "O3") (pin "3") (pinfunction "3_3") (pintype "passive"))
      (node (ref "O4") (pin "3") (pinfunction "3_3") (pintype "passive"))
      (node (ref "POWER_IN") (pin "2") (pinfunction "S_2") (pintype "passive"))
      (node (ref "POWER_IN1") (pin "2") (pinfunction "S_2") (pintype "passive"))
      (node (ref "R3") (pin "1") (pinfunction "1_1") (pintype "passive"))
      (node (ref "RESET") (pin "A") (pinfunction "P_A") (pintype "passive"))
      (node (ref "RESET") (pin "A'") (pinfunction "P1_A'") (pintype "passive"))
      (node (ref "U$1") (pin "P8.1") (pinfunction "DGND_P8.1") (pintype "bidirectional"))
      (node (ref "U$1") (pin "P8.2") (pinfunction "DGND_P8.2") (pintype "bidirectional"))
      (node (ref "U$1") (pin "P9.1") (pinfunction "DGND_P9.1") (pintype "bidirectional"))
      (node (ref "U$1") (pin "P9.2") (pinfunction "DGND_P9.2") (pintype "bidirectional"))
      (node (ref "U$12") (pin "10") (pinfunction "10_10") (pintype "passive"))
      (node (ref "U$2") (pin "6") (pinfunction "GND_2_6") (pintype "passive"))
      (node (ref "U$2") (pin "9") (pinfunction "PWPD_9") (pintype "passive"))
      (node (ref "U$3") (pin "36") (pinfunction "DVSS_4_36") (pintype "power_in"))
      (node (ref "U$3") (pin "41") (pinfunction "AVSS_1_41") (pintype "power_in"))
      (node (ref "U$3") (pin "44") (pinfunction "AVSS_2_44") (pintype "power_in"))
      (node (ref "U$3") (pin "47") (pinfunction "AVSS_3_47") (pintype "power_in"))
      (node (ref "U$5") (pin "4") (pinfunction "GND_4") (pintype "bidirectional"))
      (node (ref "U$5") (pin "PPAD") (pinfunction "PPAD_PPAD") (pintype "bidirectional"))
      (node (ref "U$6") (pin "11") (pinfunction "GND_11") (pintype "bidirectional"))
      (node (ref "U$7") (pin "11") (pinfunction "GND_11") (pintype "bidirectional"))
      (node (ref "U$8") (pin "11") (pinfunction "GND_11") (pintype "bidirectional"))
      (node (ref "U$9") (pin "11") (pinfunction "GND_11") (pintype "bidirectional"))
      (node (ref "U5") (pin "1") (pinfunction "GND_1") (pintype "passive"))
      (node (ref "X1") (pin "1") (pinfunction "S_1") (pintype "passive"))
    )
    (net (code "15") (name "LDS_RX") (class "Default")
      (node (ref "LIDAR_LASER") (pin "2") (pinfunction "2_2") (pintype "passive"))
      (node (ref "U$1") (pin "P9.24") (pinfunction "GPIO_15_P9.24") (pintype "bidirectional"))
    )
    (net (code "16") (name "LDS_TX") (class "Default")
      (node (ref "LIDAR_LASER") (pin "3") (pinfunction "3_3") (pintype "passive"))
      (node (ref "U$1") (pin "P9.26") (pinfunction "GPIO_14_P9.26") (pintype "bidirectional"))
    )
    (net (code "17") (name "LIDAR_DIR") (class "Default")
      (node (ref "U$1") (pin "P9.23") (pinfunction "GPIO_49_P9.23") (pintype "bidirectional"))
      (node (ref "U$5") (pin "6") (pinfunction "IN1_6") (pintype "bidirectional"))
    )
    (net (code "18") (name "LIDAR_OUT1") (class "Default")
      (node (ref "LIDAR_MOTOR") (pin "1") (pinfunction "1_1") (pintype "passive"))
      (node (ref "U$5") (pin "2") (pinfunction "OUT1_2") (pintype "bidirectional"))
    )
    (net (code "19") (name "LIDAR_OUT2") (class "Default")
      (node (ref "LIDAR_MOTOR") (pin "2") (pinfunction "2_2") (pintype "passive"))
      (node (ref "U$5") (pin "3") (pinfunction "OUT2_3") (pintype "bidirectional"))
    )
    (net (code "20") (name "LIDAR_PWM") (class "Default")
      (node (ref "U$1") (pin "P9.22") (pinfunction "GPIO_2_P9.22") (pintype "bidirectional"))
      (node (ref "U$5") (pin "5") (pinfunction "IN2_5") (pintype "bidirectional"))
    )
    (net (code "21") (name "MCU_ECHO1") (class "Default")
      (node (ref "U$3") (pin "20") (pinfunction "P2.5_20") (pintype "power_in"))
      (node (ref "U$6") (pin "3") (pinfunction "A2_3") (pintype "bidirectional"))
    )
    (net (code "22") (name "MCU_ECHO2") (class "Default")
      (node (ref "U$3") (pin "19") (pinfunction "P4.3_19") (pintype "power_in"))
      (node (ref "U$6") (pin "4") (pinfunction "A3_4") (pintype "bidirectional"))
    )
    (net (code "23") (name "MCU_ECHO3") (class "Default")
      (node (ref "U$3") (pin "18") (pinfunction "P4.2_18") (pintype "power_in"))
      (node (ref "U$6") (pin "5") (pinfunction "A4_5") (pintype "bidirectional"))
    )
    (net (code "24") (name "MCU_ECHO4") (class "Default")
      (node (ref "U$3") (pin "17") (pinfunction "P4.1_17") (pintype "power_in"))
      (node (ref "U$6") (pin "6") (pinfunction "A5_6") (pintype "bidirectional"))
    )
    (net (code "25") (name "MCU_ECHO5") (class "Default")
      (node (ref "U$3") (pin "16") (pinfunction "P4.0_16") (pintype "power_in"))
      (node (ref "U$6") (pin "7") (pinfunction "A6_7") (pintype "bidirectional"))
    )
    (net (code "26") (name "MCU_ECHO6") (class "Default")
      (node (ref "U$3") (pin "8") (pinfunction "P4.7_8") (pintype "power_in"))
      (node (ref "U$8") (pin "3") (pinfunction "A2_3") (pintype "bidirectional"))
    )
    (net (code "27") (name "MCU_ECHO7") (class "Default")
      (node (ref "U$3") (pin "7") (pinfunction "P3.3_7") (pintype "power_in"))
      (node (ref "U$8") (pin "4") (pinfunction "A3_4") (pintype "bidirectional"))
    )
    (net (code "28") (name "MCU_ECHO8") (class "Default")
      (node (ref "U$3") (pin "6") (pinfunction "P3.2_6") (pintype "power_in"))
      (node (ref "U$8") (pin "5") (pinfunction "A4_5") (pintype "bidirectional"))
    )
    (net (code "29") (name "MCU_ECHO9") (class "Default")
      (node (ref "U$3") (pin "5") (pinfunction "P3.1_5") (pintype "power_in"))
      (node (ref "U$8") (pin "6") (pinfunction "A5_6") (pintype "bidirectional"))
    )
    (net (code "30") (name "MCU_ECHO10") (class "Default")
      (node (ref "U$3") (pin "4") (pinfunction "P3.0_4") (pintype "power_in"))
      (node (ref "U$8") (pin "7") (pinfunction "A6_7") (pintype "bidirectional"))
    )
    (net (code "31") (name "Net-(3V-PadA)") (class "Default")
      (node (ref "3V") (pin "A") (pinfunction "A_A") (pintype "passive"))
      (node (ref "R4") (pin "1") (pinfunction "1_1") (pintype "passive"))
    )
    (net (code "32") (name "Net-(5V-PadA)") (class "Default")
      (node (ref "5V") (pin "A") (pinfunction "A_A") (pintype "passive"))
      (node (ref "R28") (pin "1") (pinfunction "1_1") (pintype "passive"))
    )
    (net (code "33") (name "Net-(BATT-PadA)") (class "Default")
      (node (ref "BATT") (pin "A") (pinfunction "A_A") (pintype "passive"))
      (node (ref "R1") (pin "1") (pinfunction "1_1") (pintype "passive"))
    )
    (net (code "34") (name "Net-(C1-Pad1)") (class "Default")
      (node (ref "C1") (pin "1") (pinfunction "1_1") (pintype "passive"))
      (node (ref "U$1") (pin "P9.5") (pinfunction "VDD_5V_P9.5") (pintype "bidirectional"))
      (node (ref "U$1") (pin "P9.6") (pinfunction "VDD_5V_P9.6") (pintype "bidirectional"))
      (node (ref "U$11") (pin "1") (pinfunction "1_1") (pintype "bidirectional"))
    )
    (net (code "35") (name "Net-(POWER_INA-S)") (class "Default")
      (node (ref "D1") (pin "A") (pinfunction "A_A") (pintype "passive"))
      (node (ref "POWER_IN") (pin "1") (pinfunction "S_1") (pintype "passive"))
    )
    (net (code "36") (name "Net-(R8-Pad1)") (class "Default")
      (node (ref "R8") (pin "1") (pinfunction "1_1") (pintype "passive"))
      (node (ref "U$12") (pin "11") (pinfunction "11_11") (pintype "passive"))
      (node (ref "U$12") (pin "12") (pinfunction "12_12") (pintype "passive"))
      (node (ref "U$12") (pin "9") (pinfunction "9_9") (pintype "passive"))
    )
    (net (code "37") (name "Net-(R9-Pad1)") (class "Default")
      (node (ref "R9") (pin "1") (pinfunction "1_1") (pintype "passive"))
      (node (ref "U$12") (pin "1") (pinfunction "1_1") (pintype "passive"))
    )
    (net (code "38") (name "Net-(U$2-ENA)") (class "Default")
      (node (ref "U$2") (pin "5") (pinfunction "ENA_5") (pintype "passive"))
      (node (ref "X1") (pin "2") (pinfunction "S_2") (pintype "passive"))
    )
    (net (code "39") (name "Net-(U$2-VSNS)") (class "Default")
      (node (ref "R2") (pin "1") (pinfunction "1_1") (pintype "passive"))
      (node (ref "R3") (pin "2") (pinfunction "2_2") (pintype "passive"))
      (node (ref "U$2") (pin "4") (pinfunction "VSNS_4") (pintype "passive"))
    )
    (net (code "40") (name "N{slash}A") (class "Default")
      (node (ref "U$5") (pin "7") (pinfunction "NSLEEP_7") (pintype "bidirectional"))
    )
    (net (code "41") (name "PH") (class "Default")
      (node (ref "C11") (pin "2") (pinfunction "2_2") (pintype "passive"))
      (node (ref "D2") (pin "3") (pinfunction "K_3") (pintype "passive"))
      (node (ref "U$10") (pin "1") (pinfunction "1_1") (pintype "passive"))
      (node (ref "U$2") (pin "8") (pinfunction "PH_8") (pintype "passive"))
    )
    (net (code "42") (name "PWM_C1") (class "Default")
      (node (ref "U$3") (pin "1") (pinfunction "P1.0_1") (pintype "power_in"))
      (node (ref "U$9") (pin "6") (pinfunction "A5_6") (pintype "bidirectional"))
    )
    (net (code "43") (name "PWM_C2") (class "Default")
      (node (ref "U$3") (pin "2") (pinfunction "P1.1_2") (pintype "power_in"))
      (node (ref "U$9") (pin "7") (pinfunction "A6_7") (pintype "bidirectional"))
    )
    (net (code "44") (name "PWM_C3") (class "Default")
      (node (ref "U$3") (pin "30") (pinfunction "P3.7_30") (pintype "power_in"))
      (node (ref "U$9") (pin "8") (pinfunction "A7_8") (pintype "bidirectional"))
    )
    (net (code "45") (name "PWM_C4") (class "Default")
      (node (ref "U$3") (pin "29") (pinfunction "P3.6_29") (pintype "power_in"))
      (node (ref "U$9") (pin "9") (pinfunction "A8_9") (pintype "bidirectional"))
    )
    (net (code "46") (name "PWM_C5") (class "Default")
      (node (ref "U$3") (pin "28") (pinfunction "P3.5_28") (pintype "power_in"))
      (node (ref "U$7") (pin "1") (pinfunction "A1_1") (pintype "bidirectional"))
    )
    (net (code "47") (name "PWM_C6") (class "Default")
      (node (ref "U$3") (pin "27") (pinfunction "P3.4_27") (pintype "power_in"))
      (node (ref "U$7") (pin "3") (pinfunction "A2_3") (pintype "bidirectional"))
    )
    (net (code "48") (name "PWM_C7") (class "Default")
      (node (ref "U$3") (pin "10") (pinfunction "P1.4_10") (pintype "power_in"))
      (node (ref "U$7") (pin "4") (pinfunction "A3_4") (pintype "bidirectional"))
    )
    (net (code "49") (name "PWM_C8") (class "Default")
      (node (ref "U$3") (pin "11") (pinfunction "P1.5_11") (pintype "power_in"))
      (node (ref "U$7") (pin "5") (pinfunction "A4_5") (pintype "bidirectional"))
    )
    (net (code "50") (name "PWM_C9") (class "Default")
      (node (ref "U$3") (pin "35") (pinfunction "P4.6_35") (pintype "power_in"))
      (node (ref "U$9") (pin "5") (pinfunction "A4_5") (pintype "bidirectional"))
    )
    (net (code "51") (name "PWM_C10") (class "Default")
      (node (ref "U$3") (pin "38") (pinfunction "P2.7_38") (pintype "power_in"))
      (node (ref "U$9") (pin "4") (pinfunction "A3_4") (pintype "bidirectional"))
    )
    (net (code "52") (name "PWM_C11") (class "Default")
      (node (ref "U$3") (pin "39") (pinfunction "P2.3_39") (pintype "power_in"))
      (node (ref "U$9") (pin "3") (pinfunction "A2_3") (pintype "bidirectional"))
    )
    (net (code "53") (name "PWM_C12") (class "Default")
      (node (ref "U$3") (pin "40") (pinfunction "P2.4_40") (pintype "power_in"))
      (node (ref "U$9") (pin "1") (pinfunction "A1_1") (pintype "bidirectional"))
    )
    (net (code "54") (name "PWM_IN_1") (class "Default")
      (node (ref "IN1") (pin "1") (pinfunction "1_1") (pintype "passive"))
      (node (ref "U$9") (pin "20") (pinfunction "B1_20") (pintype "bidirectional"))
    )
    (net (code "55") (name "PWM_IN_2") (class "Default")
      (node (ref "IN2") (pin "1") (pinfunction "1_1") (pintype "passive"))
      (node (ref "U$9") (pin "18") (pinfunction "B2_18") (pintype "bidirectional"))
    )
    (net (code "56") (name "PWM_IN_3") (class "Default")
      (node (ref "IN3") (pin "1") (pinfunction "1_1") (pintype "passive"))
      (node (ref "U$9") (pin "17") (pinfunction "B3_17") (pintype "bidirectional"))
    )
    (net (code "57") (name "PWM_IN_4") (class "Default")
      (node (ref "IN4") (pin "1") (pinfunction "1_1") (pintype "passive"))
      (node (ref "U$9") (pin "16") (pinfunction "B4_16") (pintype "bidirectional"))
    )
    (net (code "58") (name "PWM_IN_5") (class "Default")
      (node (ref "IN5") (pin "1") (pinfunction "1_1") (pintype "passive"))
      (node (ref "U$9") (pin "15") (pinfunction "B5_15") (pintype "bidirectional"))
    )
    (net (code "59") (name "PWM_IN_6") (class "Default")
      (node (ref "IN6") (pin "1") (pinfunction "1_1") (pintype "passive"))
      (node (ref "U$9") (pin "14") (pinfunction "B6_14") (pintype "bidirectional"))
    )
    (net (code "60") (name "PWM_IN_7") (class "Default")
      (node (ref "IN7") (pin "1") (pinfunction "1_1") (pintype "passive"))
      (node (ref "U$9") (pin "13") (pinfunction "B7_13") (pintype "bidirectional"))
    )
    (net (code "61") (name "PWM_IN_8") (class "Default")
      (node (ref "IN8") (pin "1") (pinfunction "1_1") (pintype "passive"))
      (node (ref "U$9") (pin "12") (pinfunction "B8_12") (pintype "bidirectional"))
    )
    (net (code "62") (name "PWM_OUT_1") (class "Default")
      (node (ref "O1") (pin "1") (pinfunction "1_1") (pintype "passive"))
      (node (ref "U$7") (pin "20") (pinfunction "B1_20") (pintype "bidirectional"))
    )
    (net (code "63") (name "PWM_OUT_2") (class "Default")
      (node (ref "O2") (pin "1") (pinfunction "1_1") (pintype "passive"))
      (node (ref "U$7") (pin "18") (pinfunction "B2_18") (pintype "bidirectional"))
    )
    (net (code "64") (name "PWM_OUT_3") (class "Default")
      (node (ref "O3") (pin "1") (pinfunction "1_1") (pintype "passive"))
      (node (ref "U$7") (pin "17") (pinfunction "B3_17") (pintype "bidirectional"))
    )
    (net (code "65") (name "PWM_OUT_4") (class "Default")
      (node (ref "O4") (pin "1") (pinfunction "1_1") (pintype "passive"))
      (node (ref "U$7") (pin "16") (pinfunction "B4_16") (pintype "bidirectional"))
    )
    (net (code "66") (name "RESET") (class "Default")
      (node (ref "C16") (pin "1") (pinfunction "1_1") (pintype "passive"))
      (node (ref "C34") (pin "1") (pinfunction "1_1") (pintype "passive"))
      (node (ref "R7") (pin "1") (pinfunction "1_1") (pintype "passive"))
      (node (ref "R8") (pin "2") (pinfunction "2_2") (pintype "passive"))
      (node (ref "RESET") (pin "B") (pinfunction "S_B") (pintype "passive"))
      (node (ref "RESET") (pin "B'") (pinfunction "S1_B'") (pintype "passive"))
      (node (ref "U$3") (pin "23") (pinfunction "RST_23") (pintype "power_in"))
    )
    (net (code "67") (name "SCL") (class "Default")
      (node (ref "U$1") (pin "P9.19") (pinfunction "I2C2_SCL_P9.19") (pintype "bidirectional"))
      (node (ref "U$4") (pin "1") (pinfunction "A_1_1") (pintype "bidirectional"))
    )
    (net (code "68") (name "SDA") (class "Default")
      (node (ref "U$1") (pin "P9.20") (pinfunction "I2C2_SDA_P9.20") (pintype "bidirectional"))
      (node (ref "U$4") (pin "4") (pinfunction "A_2_4") (pintype "bidirectional"))
    )
    (net (code "69") (name "SIMO") (class "Default")
      (node (ref "U$1") (pin "P9.30") (pinfunction "GPIO_122_P9.30") (pintype "bidirectional"))
      (node (ref "U$4") (pin "6") (pinfunction "B_2_6") (pintype "bidirectional"))
    )
    (net (code "70") (name "SIMO{slash}SDA") (class "Default")
      (node (ref "R11") (pin "1") (pinfunction "1_1") (pintype "passive"))
      (node (ref "U$3") (pin "31") (pinfunction "P1.6_31") (pintype "power_in"))
      (node (ref "U$4") (pin "5") (pinfunction "C_2_5") (pintype "bidirectional"))
    )
    (net (code "71") (name "SOMI") (class "Default")
      (node (ref "U$1") (pin "P9.29") (pinfunction "GPIO_121_P9.29") (pintype "bidirectional"))
      (node (ref "U$4") (pin "3") (pinfunction "B_1_3") (pintype "bidirectional"))
    )
    (net (code "72") (name "SOMI{slash}SCL") (class "Default")
      (node (ref "R10") (pin "1") (pinfunction "1_1") (pintype "passive"))
      (node (ref "U$3") (pin "32") (pinfunction "P1.7_32") (pintype "power_in"))
      (node (ref "U$4") (pin "2") (pinfunction "C_1_2") (pintype "bidirectional"))
    )
    (net (code "73") (name "SPI_CLK") (class "Default")
      (node (ref "U$1") (pin "P9.31") (pinfunction "GPIO_120_P9.31") (pintype "bidirectional"))
      (node (ref "U$3") (pin "26") (pinfunction "P2.2_26") (pintype "power_in"))
    )
    (net (code "74") (name "SPI_SL") (class "Default")
      (node (ref "SPDT") (pin "2") (pinfunction "C1_2") (pintype "bidirectional"))
      (node (ref "U$3") (pin "9") (pinfunction "P1.3_9") (pintype "power_in"))
    )
    (net (code "75") (name "SPI_SL0") (class "Default")
      (node (ref "SPDT") (pin "1") (pinfunction "A1_1") (pintype "bidirectional"))
      (node (ref "U$1") (pin "P9.28") (pinfunction "GPIO_123_P9.28") (pintype "bidirectional"))
    )
    (net (code "76") (name "SPI_SL1") (class "Default")
      (node (ref "SPDT") (pin "3") (pinfunction "B1_3") (pintype "bidirectional"))
      (node (ref "U$1") (pin "P9.42") (pinfunction "GPIO_7_P9.42") (pintype "bidirectional"))
    )
    (net (code "77") (name "TCK") (class "Default")
      (node (ref "U$12") (pin "8") (pinfunction "8_8") (pintype "passive"))
      (node (ref "U$3") (pin "15") (pinfunction "PJ.3_15") (pintype "power_in"))
    )
    (net (code "78") (name "TDI") (class "Default")
      (node (ref "U$12") (pin "4") (pinfunction "4_4") (pintype "passive"))
      (node (ref "U$3") (pin "13") (pinfunction "PJ.1_13") (pintype "power_in"))
    )
    (net (code "79") (name "TDO") (class "Default")
      (node (ref "U$12") (pin "2") (pinfunction "2_2") (pintype "passive"))
      (node (ref "U$3") (pin "12") (pinfunction "PJ.0_12") (pintype "power_in"))
    )
    (net (code "80") (name "TEST") (class "Default")
      (node (ref "U$12") (pin "7") (pinfunction "7_7") (pintype "passive"))
      (node (ref "U$3") (pin "22") (pinfunction "TEST_22") (pintype "power_in"))
    )
    (net (code "81") (name "TMS") (class "Default")
      (node (ref "U$12") (pin "6") (pinfunction "6_6") (pintype "passive"))
      (node (ref "U$3") (pin "14") (pinfunction "PJ.2_14") (pintype "power_in"))
    )
    (net (code "82") (name "TRIG_1") (class "Default")
      (node (ref "J1") (pin "2") (pinfunction "2_2") (pintype "passive"))
      (node (ref "U$3") (pin "21") (pinfunction "P2.6_21") (pintype "power_in"))
    )
    (net (code "83") (name "TRIG_2") (class "Default")
      (node (ref "J1") (pin "6") (pinfunction "6_6") (pintype "passive"))
      (node (ref "U$3") (pin "33") (pinfunction "P4.4_33") (pintype "power_in"))
    )
    (net (code "84") (name "TRIG_3") (class "Default")
      (node (ref "J1") (pin "10") (pinfunction "10_10") (pintype "passive"))
      (node (ref "U$3") (pin "34") (pinfunction "P4.5_34") (pintype "power_in"))
    )
    (net (code "85") (name "TRIG_4") (class "Default")
      (node (ref "J1") (pin "14") (pinfunction "14_14") (pintype "passive"))
      (node (ref "U$3") (pin "25") (pinfunction "P2.1_25") (pintype "power_in"))
    )
    (net (code "86") (name "TRIG_5") (class "Default")
      (node (ref "J1") (pin "18") (pinfunction "18_18") (pintype "passive"))
      (node (ref "U$3") (pin "24") (pinfunction "P2.0_24") (pintype "power_in"))
    )
    (net (code "87") (name "TRIG_6") (class "Default")
      (node (ref "J2") (pin "2") (pinfunction "2_2") (pintype "passive"))
      (node (ref "U$3") (pin "3") (pinfunction "P1.2_3") (pintype "power_in"))
    )
    (net (code "88") (name "TRIG_7") (class "Default")
      (node (ref "J2") (pin "6") (pinfunction "6_6") (pintype "passive"))
      (node (ref "U$3") (pin "46") (pinfunction "PJ.5_46") (pintype "power_in"))
    )
    (net (code "89") (name "TRIG_8") (class "Default")
      (node (ref "J2") (pin "10") (pinfunction "10_10") (pintype "passive"))
      (node (ref "U$3") (pin "45") (pinfunction "PJ.4_45") (pintype "power_in"))
    )
    (net (code "90") (name "TRIG_9") (class "Default")
      (node (ref "J2") (pin "14") (pinfunction "14_14") (pintype "passive"))
      (node (ref "U$3") (pin "43") (pinfunction "PJ.7_43") (pintype "power_in"))
    )
    (net (code "91") (name "TRIG_10") (class "Default")
      (node (ref "J2") (pin "18") (pinfunction "18_18") (pintype "passive"))
      (node (ref "U$3") (pin "42") (pinfunction "PJ.6_42") (pintype "power_in"))
    )
    (net (code "92") (name "T_PAD") (class "Default")
      (node (ref "U$3") (pin "49") (pinfunction "T_PAD_49") (pintype "power_in"))
    )
    (net (code "93") (name "VCC") (class "Default")
      (node (ref "C10") (pin "2") (pinfunction "2_2") (pintype "passive"))
      (node (ref "C19") (pin "2") (pinfunction "2_2") (pintype "passive"))
      (node (ref "C20") (pin "2") (pinfunction "2_2") (pintype "passive"))
      (node (ref "C21") (pin "2") (pinfunction "2_2") (pintype "passive"))
      (node (ref "D1") (pin "C") (pinfunction "C_C") (pintype "passive"))
      (node (ref "R1") (pin "2") (pinfunction "2_2") (pintype "passive"))
      (node (ref "U$2") (pin "7") (pinfunction "VIN_7") (pintype "passive"))
    )
    (net (code "94") (name "unconnected-(U$1A-GPIO_8-PadP8.35)") (class "Default")
      (node (ref "U$1") (pin "P8.35") (pinfunction "GPIO_8_P8.35") (pintype "bidirectional"))
    )
    (net (code "95") (name "unconnected-(U$1A-GPIO_9-PadP8.33)") (class "Default")
      (node (ref "U$1") (pin "P8.33") (pinfunction "GPIO_9_P8.33") (pintype "bidirectional"))
    )
    (net (code "96") (name "unconnected-(U$1A-GPIO_10-PadP8.31)") (class "Default")
      (node (ref "U$1") (pin "P8.31") (pinfunction "GPIO_10_P8.31") (pintype "bidirectional"))
    )
    (net (code "97") (name "unconnected-(U$1A-GPIO_11-PadP8.32)") (class "Default")
      (node (ref "U$1") (pin "P8.32") (pinfunction "GPIO_11_P8.32") (pintype "bidirectional"))
    )
    (net (code "98") (name "unconnected-(U$1A-GPIO_22-PadP8.19)") (class "Default")
      (node (ref "U$1") (pin "P8.19") (pinfunction "GPIO_22_P8.19") (pintype "bidirectional"))
    )
    (net (code "99") (name "unconnected-(U$1A-GPIO_23-PadP8.13)") (class "Default")
      (node (ref "U$1") (pin "P8.13") (pinfunction "GPIO_23_P8.13") (pintype "bidirectional"))
    )
    (net (code "100") (name "unconnected-(U$1A-GPIO_26-PadP8.14)") (class "Default")
      (node (ref "U$1") (pin "P8.14") (pinfunction "GPIO_26_P8.14") (pintype "bidirectional"))
    )
    (net (code "101") (name "unconnected-(U$1A-GPIO_27-PadP8.17)") (class "Default")
      (node (ref "U$1") (pin "P8.17") (pinfunction "GPIO_27_P8.17") (pintype "bidirectional"))
    )
    (net (code "102") (name "unconnected-(U$1A-GPIO_32-PadP8.25)") (class "Default")
      (node (ref "U$1") (pin "P8.25") (pinfunction "GPIO_32_P8.25") (pintype "bidirectional"))
    )
    (net (code "103") (name "unconnected-(U$1A-GPIO_33-PadP8.24)") (class "Default")
      (node (ref "U$1") (pin "P8.24") (pinfunction "GPIO_33_P8.24") (pintype "bidirectional"))
    )
    (net (code "104") (name "unconnected-(U$1A-GPIO_34-PadP8.5)") (class "Default")
      (node (ref "U$1") (pin "P8.5") (pinfunction "GPIO_34_P8.5") (pintype "bidirectional"))
    )
    (net (code "105") (name "unconnected-(U$1A-GPIO_35-PadP8.6)") (class "Default")
      (node (ref "U$1") (pin "P8.6") (pinfunction "GPIO_35_P8.6") (pintype "bidirectional"))
    )
    (net (code "106") (name "unconnected-(U$1A-GPIO_36-PadP8.23)") (class "Default")
      (node (ref "U$1") (pin "P8.23") (pinfunction "GPIO_36_P8.23") (pintype "bidirectional"))
    )
    (net (code "107") (name "unconnected-(U$1A-GPIO_37-PadP8.22)") (class "Default")
      (node (ref "U$1") (pin "P8.22") (pinfunction "GPIO_37_P8.22") (pintype "bidirectional"))
    )
    (net (code "108") (name "unconnected-(U$1A-GPIO_38-PadP8.3)") (class "Default")
      (node (ref "U$1") (pin "P8.3") (pinfunction "GPIO_38_P8.3") (pintype "bidirectional"))
    )
    (net (code "109") (name "unconnected-(U$1A-GPIO_39-PadP8.4)") (class "Default")
      (node (ref "U$1") (pin "P8.4") (pinfunction "GPIO_39_P8.4") (pintype "bidirectional"))
    )
    (net (code "110") (name "unconnected-(U$1A-GPIO_44-PadP8.12)") (class "Default")
      (node (ref "U$1") (pin "P8.12") (pinfunction "GPIO_44_P8.12") (pintype "bidirectional"))
    )
    (net (code "111") (name "unconnected-(U$1A-GPIO_45-PadP8.11)") (class "Default")
      (node (ref "U$1") (pin "P8.11") (pinfunction "GPIO_45_P8.11") (pintype "bidirectional"))
    )
    (net (code "112") (name "unconnected-(U$1A-GPIO_46-PadP8.16)") (class "Default")
      (node (ref "U$1") (pin "P8.16") (pinfunction "GPIO_46_P8.16") (pintype "bidirectional"))
    )
    (net (code "113") (name "unconnected-(U$1A-GPIO_47-PadP8.15)") (class "Default")
      (node (ref "U$1") (pin "P8.15") (pinfunction "GPIO_47_P8.15") (pintype "bidirectional"))
    )
    (net (code "114") (name "unconnected-(U$1A-GPIO_61-PadP8.26)") (class "Default")
      (node (ref "U$1") (pin "P8.26") (pinfunction "GPIO_61_P8.26") (pintype "bidirectional"))
    )
    (net (code "115") (name "unconnected-(U$1A-GPIO_62-PadP8.21)") (class "Default")
      (node (ref "U$1") (pin "P8.21") (pinfunction "GPIO_62_P8.21") (pintype "bidirectional"))
    )
    (net (code "116") (name "unconnected-(U$1A-GPIO_63-PadP8.20)") (class "Default")
      (node (ref "U$1") (pin "P8.20") (pinfunction "GPIO_63_P8.20") (pintype "bidirectional"))
    )
    (net (code "117") (name "unconnected-(U$1A-GPIO_65-PadP8.18)") (class "Default")
      (node (ref "U$1") (pin "P8.18") (pinfunction "GPIO_65_P8.18") (pintype "bidirectional"))
    )
    (net (code "118") (name "unconnected-(U$1A-GPIO_66-PadP8.7)") (class "Default")
      (node (ref "U$1") (pin "P8.7") (pinfunction "GPIO_66_P8.7") (pintype "bidirectional"))
    )
    (net (code "119") (name "unconnected-(U$1A-GPIO_67-PadP8.8)") (class "Default")
      (node (ref "U$1") (pin "P8.8") (pinfunction "GPIO_67_P8.8") (pintype "bidirectional"))
    )
    (net (code "120") (name "unconnected-(U$1A-GPIO_68-PadP8.10)") (class "Default")
      (node (ref "U$1") (pin "P8.10") (pinfunction "GPIO_68_P8.10") (pintype "bidirectional"))
    )
    (net (code "121") (name "unconnected-(U$1A-GPIO_69-PadP8.9)") (class "Default")
      (node (ref "U$1") (pin "P8.9") (pinfunction "GPIO_69_P8.9") (pintype "bidirectional"))
    )
    (net (code "122") (name "unconnected-(U$1A-GPIO_70-PadP8.45)") (class "Default")
      (node (ref "U$1") (pin "P8.45") (pinfunction "GPIO_70_P8.45") (pintype "bidirectional"))
    )
    (net (code "123") (name "unconnected-(U$1A-GPIO_71-PadP8.46)") (class "Default")
      (node (ref "U$1") (pin "P8.46") (pinfunction "GPIO_71_P8.46") (pintype "bidirectional"))
    )
    (net (code "124") (name "unconnected-(U$1A-GPIO_72-PadP8.43)") (class "Default")
      (node (ref "U$1") (pin "P8.43") (pinfunction "GPIO_72_P8.43") (pintype "bidirectional"))
    )
    (net (code "125") (name "unconnected-(U$1A-GPIO_73-PadP8.44)") (class "Default")
      (node (ref "U$1") (pin "P8.44") (pinfunction "GPIO_73_P8.44") (pintype "bidirectional"))
    )
    (net (code "126") (name "unconnected-(U$1A-GPIO_74-PadP8.41)") (class "Default")
      (node (ref "U$1") (pin "P8.41") (pinfunction "GPIO_74_P8.41") (pintype "bidirectional"))
    )
    (net (code "127") (name "unconnected-(U$1A-GPIO_75-PadP8.42)") (class "Default")
      (node (ref "U$1") (pin "P8.42") (pinfunction "GPIO_75_P8.42") (pintype "bidirectional"))
    )
    (net (code "128") (name "unconnected-(U$1A-GPIO_76-PadP8.39)") (class "Default")
      (node (ref "U$1") (pin "P8.39") (pinfunction "GPIO_76_P8.39") (pintype "bidirectional"))
    )
    (net (code "129") (name "unconnected-(U$1A-GPIO_77-PadP8.40)") (class "Default")
      (node (ref "U$1") (pin "P8.40") (pinfunction "GPIO_77_P8.40") (pintype "bidirectional"))
    )
    (net (code "130") (name "unconnected-(U$1A-GPIO_78-PadP8.37)") (class "Default")
      (node (ref "U$1") (pin "P8.37") (pinfunction "GPIO_78_P8.37") (pintype "bidirectional"))
    )
    (net (code "131") (name "unconnected-(U$1A-GPIO_79-PadP8.38)") (class "Default")
      (node (ref "U$1") (pin "P8.38") (pinfunction "GPIO_79_P8.38") (pintype "bidirectional"))
    )
    (net (code "132") (name "unconnected-(U$1A-GPIO_80-PadP8.36)") (class "Default")
      (node (ref "U$1") (pin "P8.36") (pinfunction "GPIO_80_P8.36") (pintype "bidirectional"))
    )
    (net (code "133") (name "unconnected-(U$1A-GPIO_81-PadP8.34)") (class "Default")
      (node (ref "U$1") (pin "P8.34") (pinfunction "GPIO_81_P8.34") (pintype "bidirectional"))
    )
    (net (code "134") (name "unconnected-(U$1A-GPIO_86-PadP8.27)") (class "Default")
      (node (ref "U$1") (pin "P8.27") (pinfunction "GPIO_86_P8.27") (pintype "bidirectional"))
    )
    (net (code "135") (name "unconnected-(U$1A-GPIO_87-PadP8.29)") (class "Default")
      (node (ref "U$1") (pin "P8.29") (pinfunction "GPIO_87_P8.29") (pintype "bidirectional"))
    )
    (net (code "136") (name "unconnected-(U$1A-GPIO_88-PadP8.28)") (class "Default")
      (node (ref "U$1") (pin "P8.28") (pinfunction "GPIO_88_P8.28") (pintype "bidirectional"))
    )
    (net (code "137") (name "unconnected-(U$1A-GPIO_89-PadP8.30)") (class "Default")
      (node (ref "U$1") (pin "P8.30") (pinfunction "GPIO_89_P8.30") (pintype "bidirectional"))
    )
    (net (code "138") (name "unconnected-(U$1B-AIN0-PadP9.39)") (class "Default")
      (node (ref "U$1") (pin "P9.39") (pinfunction "AIN0_P9.39") (pintype "bidirectional"))
    )
    (net (code "139") (name "unconnected-(U$1B-AIN1-PadP9.40)") (class "Default")
      (node (ref "U$1") (pin "P9.40") (pinfunction "AIN1_P9.40") (pintype "bidirectional"))
    )
    (net (code "140") (name "unconnected-(U$1B-AIN2-PadP9.37)") (class "Default")
      (node (ref "U$1") (pin "P9.37") (pinfunction "AIN2_P9.37") (pintype "bidirectional"))
    )
    (net (code "141") (name "unconnected-(U$1B-AIN3-PadP9.38)") (class "Default")
      (node (ref "U$1") (pin "P9.38") (pinfunction "AIN3_P9.38") (pintype "bidirectional"))
    )
    (net (code "142") (name "unconnected-(U$1B-AIN4-PadP9.33)") (class "Default")
      (node (ref "U$1") (pin "P9.33") (pinfunction "AIN4_P9.33") (pintype "bidirectional"))
    )
    (net (code "143") (name "unconnected-(U$1B-AIN5-PadP9.36)") (class "Default")
      (node (ref "U$1") (pin "P9.36") (pinfunction "AIN5_P9.36") (pintype "bidirectional"))
    )
    (net (code "144") (name "unconnected-(U$1B-AIN6-PadP9.35)") (class "Default")
      (node (ref "U$1") (pin "P9.35") (pinfunction "AIN6_P9.35") (pintype "bidirectional"))
    )
    (net (code "145") (name "unconnected-(U$1B-DGND-PadP9.43)") (class "Default")
      (node (ref "U$1") (pin "P9.43") (pinfunction "DGND_P9.43") (pintype "bidirectional"))
    )
    (net (code "146") (name "unconnected-(U$1B-DGND-PadP9.44)") (class "Default")
      (node (ref "U$1") (pin "P9.44") (pinfunction "DGND_P9.44") (pintype "bidirectional"))
    )
    (net (code "147") (name "unconnected-(U$1B-DGND-PadP9.45)") (class "Default")
      (node (ref "U$1") (pin "P9.45") (pinfunction "DGND_P9.45") (pintype "bidirectional"))
    )
    (net (code "148") (name "unconnected-(U$1B-DGND-PadP9.46)") (class "Default")
      (node (ref "U$1") (pin "P9.46") (pinfunction "DGND_P9.46") (pintype "bidirectional"))
    )
    (net (code "149") (name "unconnected-(U$1B-GNDA_ADC-PadP9.34)") (class "Default")
      (node (ref "U$1") (pin "P9.34") (pinfunction "GNDA_ADC_P9.34") (pintype "bidirectional"))
    )
    (net (code "150") (name "unconnected-(U$1B-GPIO_3-PadP9.21)") (class "Default")
      (node (ref "U$1") (pin "P9.21") (pinfunction "GPIO_3_P9.21") (pintype "bidirectional"))
    )
    (net (code "151") (name "unconnected-(U$1B-GPIO_4-PadP9.17)") (class "Default")
      (node (ref "U$1") (pin "P9.17") (pinfunction "GPIO_4_P9.17") (pintype "bidirectional"))
    )
    (net (code "152") (name "unconnected-(U$1B-GPIO_5-PadP9.18)") (class "Default")
      (node (ref "U$1") (pin "P9.18") (pinfunction "GPIO_5_P9.18") (pintype "bidirectional"))
    )
    (net (code "153") (name "unconnected-(U$1B-GPIO_20-PadP9.41)") (class "Default")
      (node (ref "U$1") (pin "P9.41") (pinfunction "GPIO_20_P9.41") (pintype "bidirectional"))
    )
    (net (code "154") (name "unconnected-(U$1B-GPIO_30-PadP9.11)") (class "Default")
      (node (ref "U$1") (pin "P9.11") (pinfunction "GPIO_30_P9.11") (pintype "bidirectional"))
    )
    (net (code "155") (name "unconnected-(U$1B-GPIO_31-PadP9.13)") (class "Default")
      (node (ref "U$1") (pin "P9.13") (pinfunction "GPIO_31_P9.13") (pintype "bidirectional"))
    )
    (net (code "156") (name "unconnected-(U$1B-GPIO_40-PadP9.14)") (class "Default")
      (node (ref "U$1") (pin "P9.14") (pinfunction "GPIO_40_P9.14") (pintype "bidirectional"))
    )
    (net (code "157") (name "unconnected-(U$1B-GPIO_48-PadP9.15)") (class "Default")
      (node (ref "U$1") (pin "P9.15") (pinfunction "GPIO_48_P9.15") (pintype "bidirectional"))
    )
    (net (code "158") (name "unconnected-(U$1B-GPIO_51-PadP9.16)") (class "Default")
      (node (ref "U$1") (pin "P9.16") (pinfunction "GPIO_51_P9.16") (pintype "bidirectional"))
    )
    (net (code "159") (name "unconnected-(U$1B-GPIO_60-PadP9.12)") (class "Default")
      (node (ref "U$1") (pin "P9.12") (pinfunction "GPIO_60_P9.12") (pintype "bidirectional"))
    )
    (net (code "160") (name "unconnected-(U$1B-GPIO_117-PadP9.25)") (class "Default")
      (node (ref "U$1") (pin "P9.25") (pinfunction "GPIO_117_P9.25") (pintype "bidirectional"))
    )
    (net (code "161") (name "unconnected-(U$1B-GPIO_125-PadP9.27)") (class "Default")
      (node (ref "U$1") (pin "P9.27") (pinfunction "GPIO_125_P9.27") (pintype "bidirectional"))
    )
    (net (code "162") (name "unconnected-(U$1B-PWR_BUT-PadP9.9)") (class "Default")
      (node (ref "U$1") (pin "P9.9") (pinfunction "PWR_BUT_P9.9") (pintype "bidirectional"))
    )
    (net (code "163") (name "unconnected-(U$1B-SYS_5V-PadP9.7)") (class "Default")
      (node (ref "U$1") (pin "P9.7") (pinfunction "SYS_5V_P9.7") (pintype "bidirectional"))
    )
    (net (code "164") (name "unconnected-(U$1B-SYS_5V-PadP9.8)") (class "Default")
      (node (ref "U$1") (pin "P9.8") (pinfunction "SYS_5V_P9.8") (pintype "bidirectional"))
    )
    (net (code "165") (name "unconnected-(U$1B-SYS_RESET~{N}-PadP9.10)") (class "Default")
      (node (ref "U$1") (pin "P9.10") (pinfunction "SYS_RESET~{N}_P9.10") (pintype "bidirectional"))
    )
    (net (code "166") (name "unconnected-(U$1B-VDD_3V3-PadP9.3)") (class "Default")
      (node (ref "U$1") (pin "P9.3") (pinfunction "VDD_3V3_P9.3") (pintype "bidirectional"))
    )
    (net (code "167") (name "unconnected-(U$1B-VDD_3V3-PadP9.4)") (class "Default")
      (node (ref "U$1") (pin "P9.4") (pinfunction "VDD_3V3_P9.4") (pintype "bidirectional"))
    )
    (net (code "168") (name "unconnected-(U$1B-VDD_ADC-PadP9.32)") (class "Default")
      (node (ref "U$1") (pin "P9.32") (pinfunction "VDD_ADC_P9.32") (pintype "bidirectional"))
    )
    (net (code "169") (name "unconnected-(U$6-A1-Pad1)") (class "Default")
      (node (ref "U$6") (pin "1") (pinfunction "A1_1") (pintype "bidirectional"))
    )
    (net (code "170") (name "unconnected-(U$6-A7-Pad8)") (class "Default")
      (node (ref "U$6") (pin "8") (pinfunction "A7_8") (pintype "bidirectional"))
    )
    (net (code "171") (name "unconnected-(U$6-A8-Pad9)") (class "Default")
      (node (ref "U$6") (pin "9") (pinfunction "A8_9") (pintype "bidirectional"))
    )
    (net (code "172") (name "unconnected-(U$6-B1-Pad20)") (class "Default")
      (node (ref "U$6") (pin "20") (pinfunction "B1_20") (pintype "bidirectional"))
    )
    (net (code "173") (name "unconnected-(U$6-B7-Pad13)") (class "Default")
      (node (ref "U$6") (pin "13") (pinfunction "B7_13") (pintype "bidirectional"))
    )
    (net (code "174") (name "unconnected-(U$6-B8-Pad12)") (class "Default")
      (node (ref "U$6") (pin "12") (pinfunction "B8_12") (pintype "bidirectional"))
    )
    (net (code "175") (name "unconnected-(U$7-A5-Pad6)") (class "Default")
      (node (ref "U$7") (pin "6") (pinfunction "A5_6") (pintype "bidirectional"))
    )
    (net (code "176") (name "unconnected-(U$7-A6-Pad7)") (class "Default")
      (node (ref "U$7") (pin "7") (pinfunction "A6_7") (pintype "bidirectional"))
    )
    (net (code "177") (name "unconnected-(U$7-A7-Pad8)") (class "Default")
      (node (ref "U$7") (pin "8") (pinfunction "A7_8") (pintype "bidirectional"))
    )
    (net (code "178") (name "unconnected-(U$7-A8-Pad9)") (class "Default")
      (node (ref "U$7") (pin "9") (pinfunction "A8_9") (pintype "bidirectional"))
    )
    (net (code "179") (name "unconnected-(U$7-B5-Pad15)") (class "Default")
      (node (ref "U$7") (pin "15") (pinfunction "B5_15") (pintype "bidirectional"))
    )
    (net (code "180") (name "unconnected-(U$7-B6-Pad14)") (class "Default")
      (node (ref "U$7") (pin "14") (pinfunction "B6_14") (pintype "bidirectional"))
    )
    (net (code "181") (name "unconnected-(U$7-B7-Pad13)") (class "Default")
      (node (ref "U$7") (pin "13") (pinfunction "B7_13") (pintype "bidirectional"))
    )
    (net (code "182") (name "unconnected-(U$7-B8-Pad12)") (class "Default")
      (node (ref "U$7") (pin "12") (pinfunction "B8_12") (pintype "bidirectional"))
    )
    (net (code "183") (name "unconnected-(U$8-A1-Pad1)") (class "Default")
      (node (ref "U$8") (pin "1") (pinfunction "A1_1") (pintype "bidirectional"))
    )
    (net (code "184") (name "unconnected-(U$8-A7-Pad8)") (class "Default")
      (node (ref "U$8") (pin "8") (pinfunction "A7_8") (pintype "bidirectional"))
    )
    (net (code "185") (name "unconnected-(U$8-A8-Pad9)") (class "Default")
      (node (ref "U$8") (pin "9") (pinfunction "A8_9") (pintype "bidirectional"))
    )
    (net (code "186") (name "unconnected-(U$8-B1-Pad20)") (class "Default")
      (node (ref "U$8") (pin "20") (pinfunction "B1_20") (pintype "bidirectional"))
    )
    (net (code "187") (name "unconnected-(U$8-B7-Pad13)") (class "Default")
      (node (ref "U$8") (pin "13") (pinfunction "B7_13") (pintype "bidirectional"))
    )
    (net (code "188") (name "unconnected-(U$8-B8-Pad12)") (class "Default")
      (node (ref "U$8") (pin "12") (pinfunction "B8_12") (pintype "bidirectional"))
    )
    (net (code "189") (name "unconnected-(U$12-Pad3)") (class "Default")
      (node (ref "U$12") (pin "3") (pinfunction "3_3") (pintype "passive"))
    )
    (net (code "190") (name "unconnected-(U$12-Pad5)") (class "Default")
      (node (ref "U$12") (pin "5") (pinfunction "5_5") (pintype "passive"))
    )
    (net (code "191") (name "unconnected-(U$12-Pad13)") (class "Default")
      (node (ref "U$12") (pin "13") (pinfunction "13_13") (pintype "passive"))
    )
    (net (code "192") (name "unconnected-(U$12-Pad14)") (class "Default")
      (node (ref "U$12") (pin "14") (pinfunction "14_14") (pintype "passive"))
    )
    (net (code "193") (name "unconnected-(U5-OUT-Pad2)") (class "Default")
      (node (ref "U5") (pin "2") (pinfunction "OUT_2") (pintype "output"))
    )
  )
)
